# haasoscope_pro_adc_board.net
KiCad netlist of a schematic drawn in EAGLE
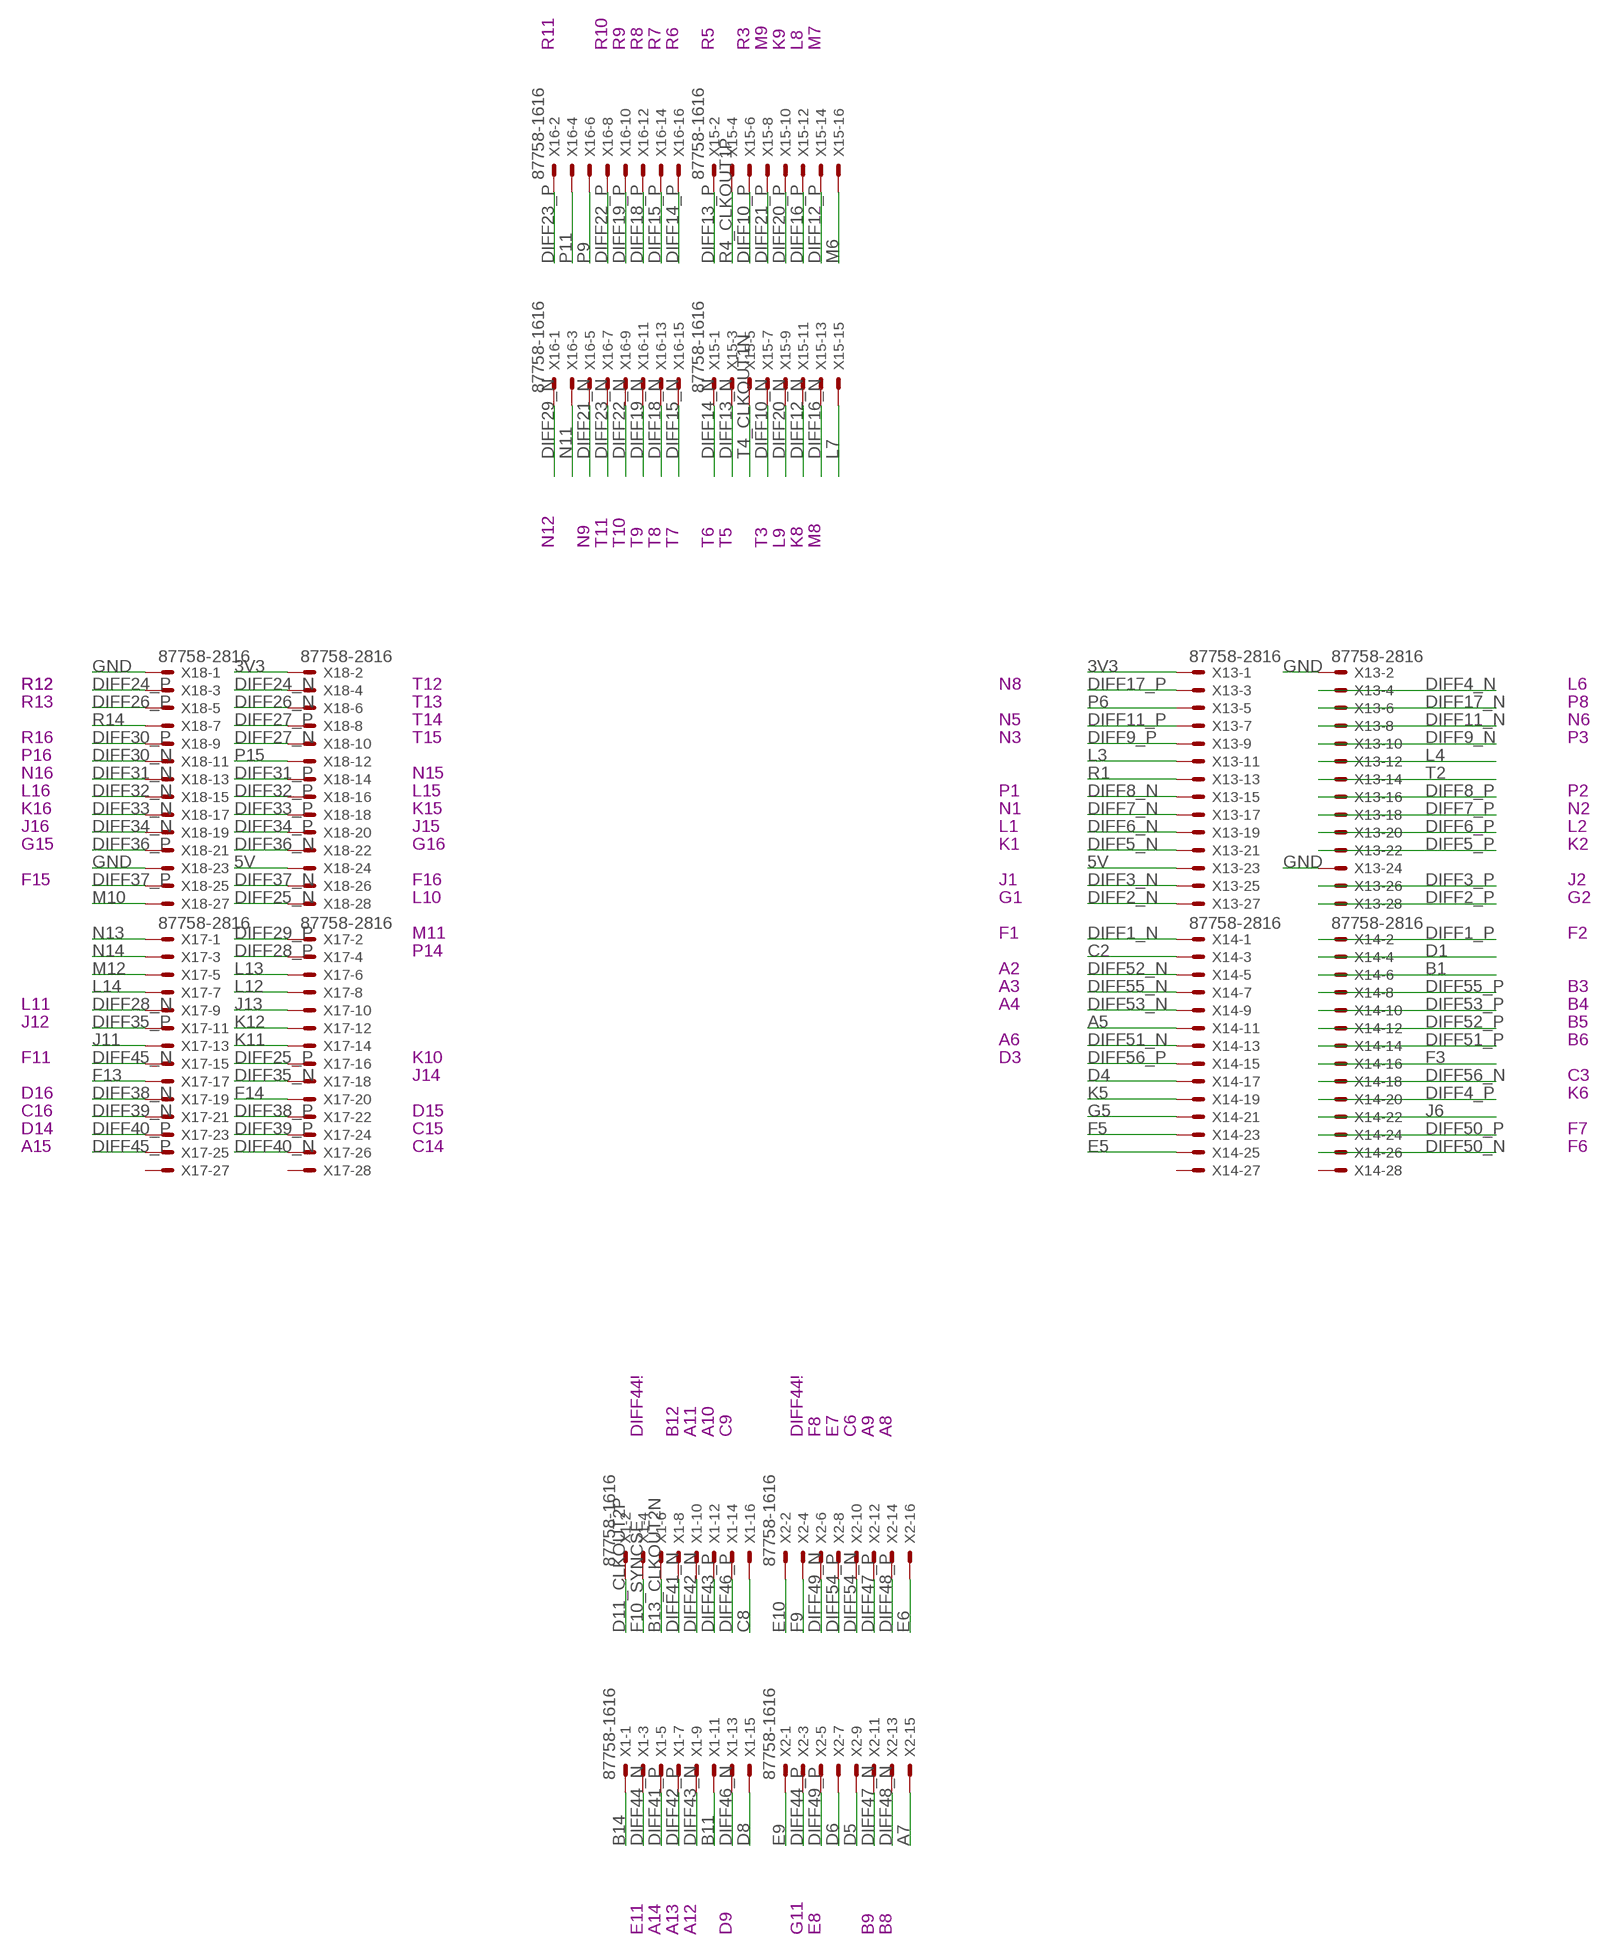
[diagram p0: schematic, sheet 1]
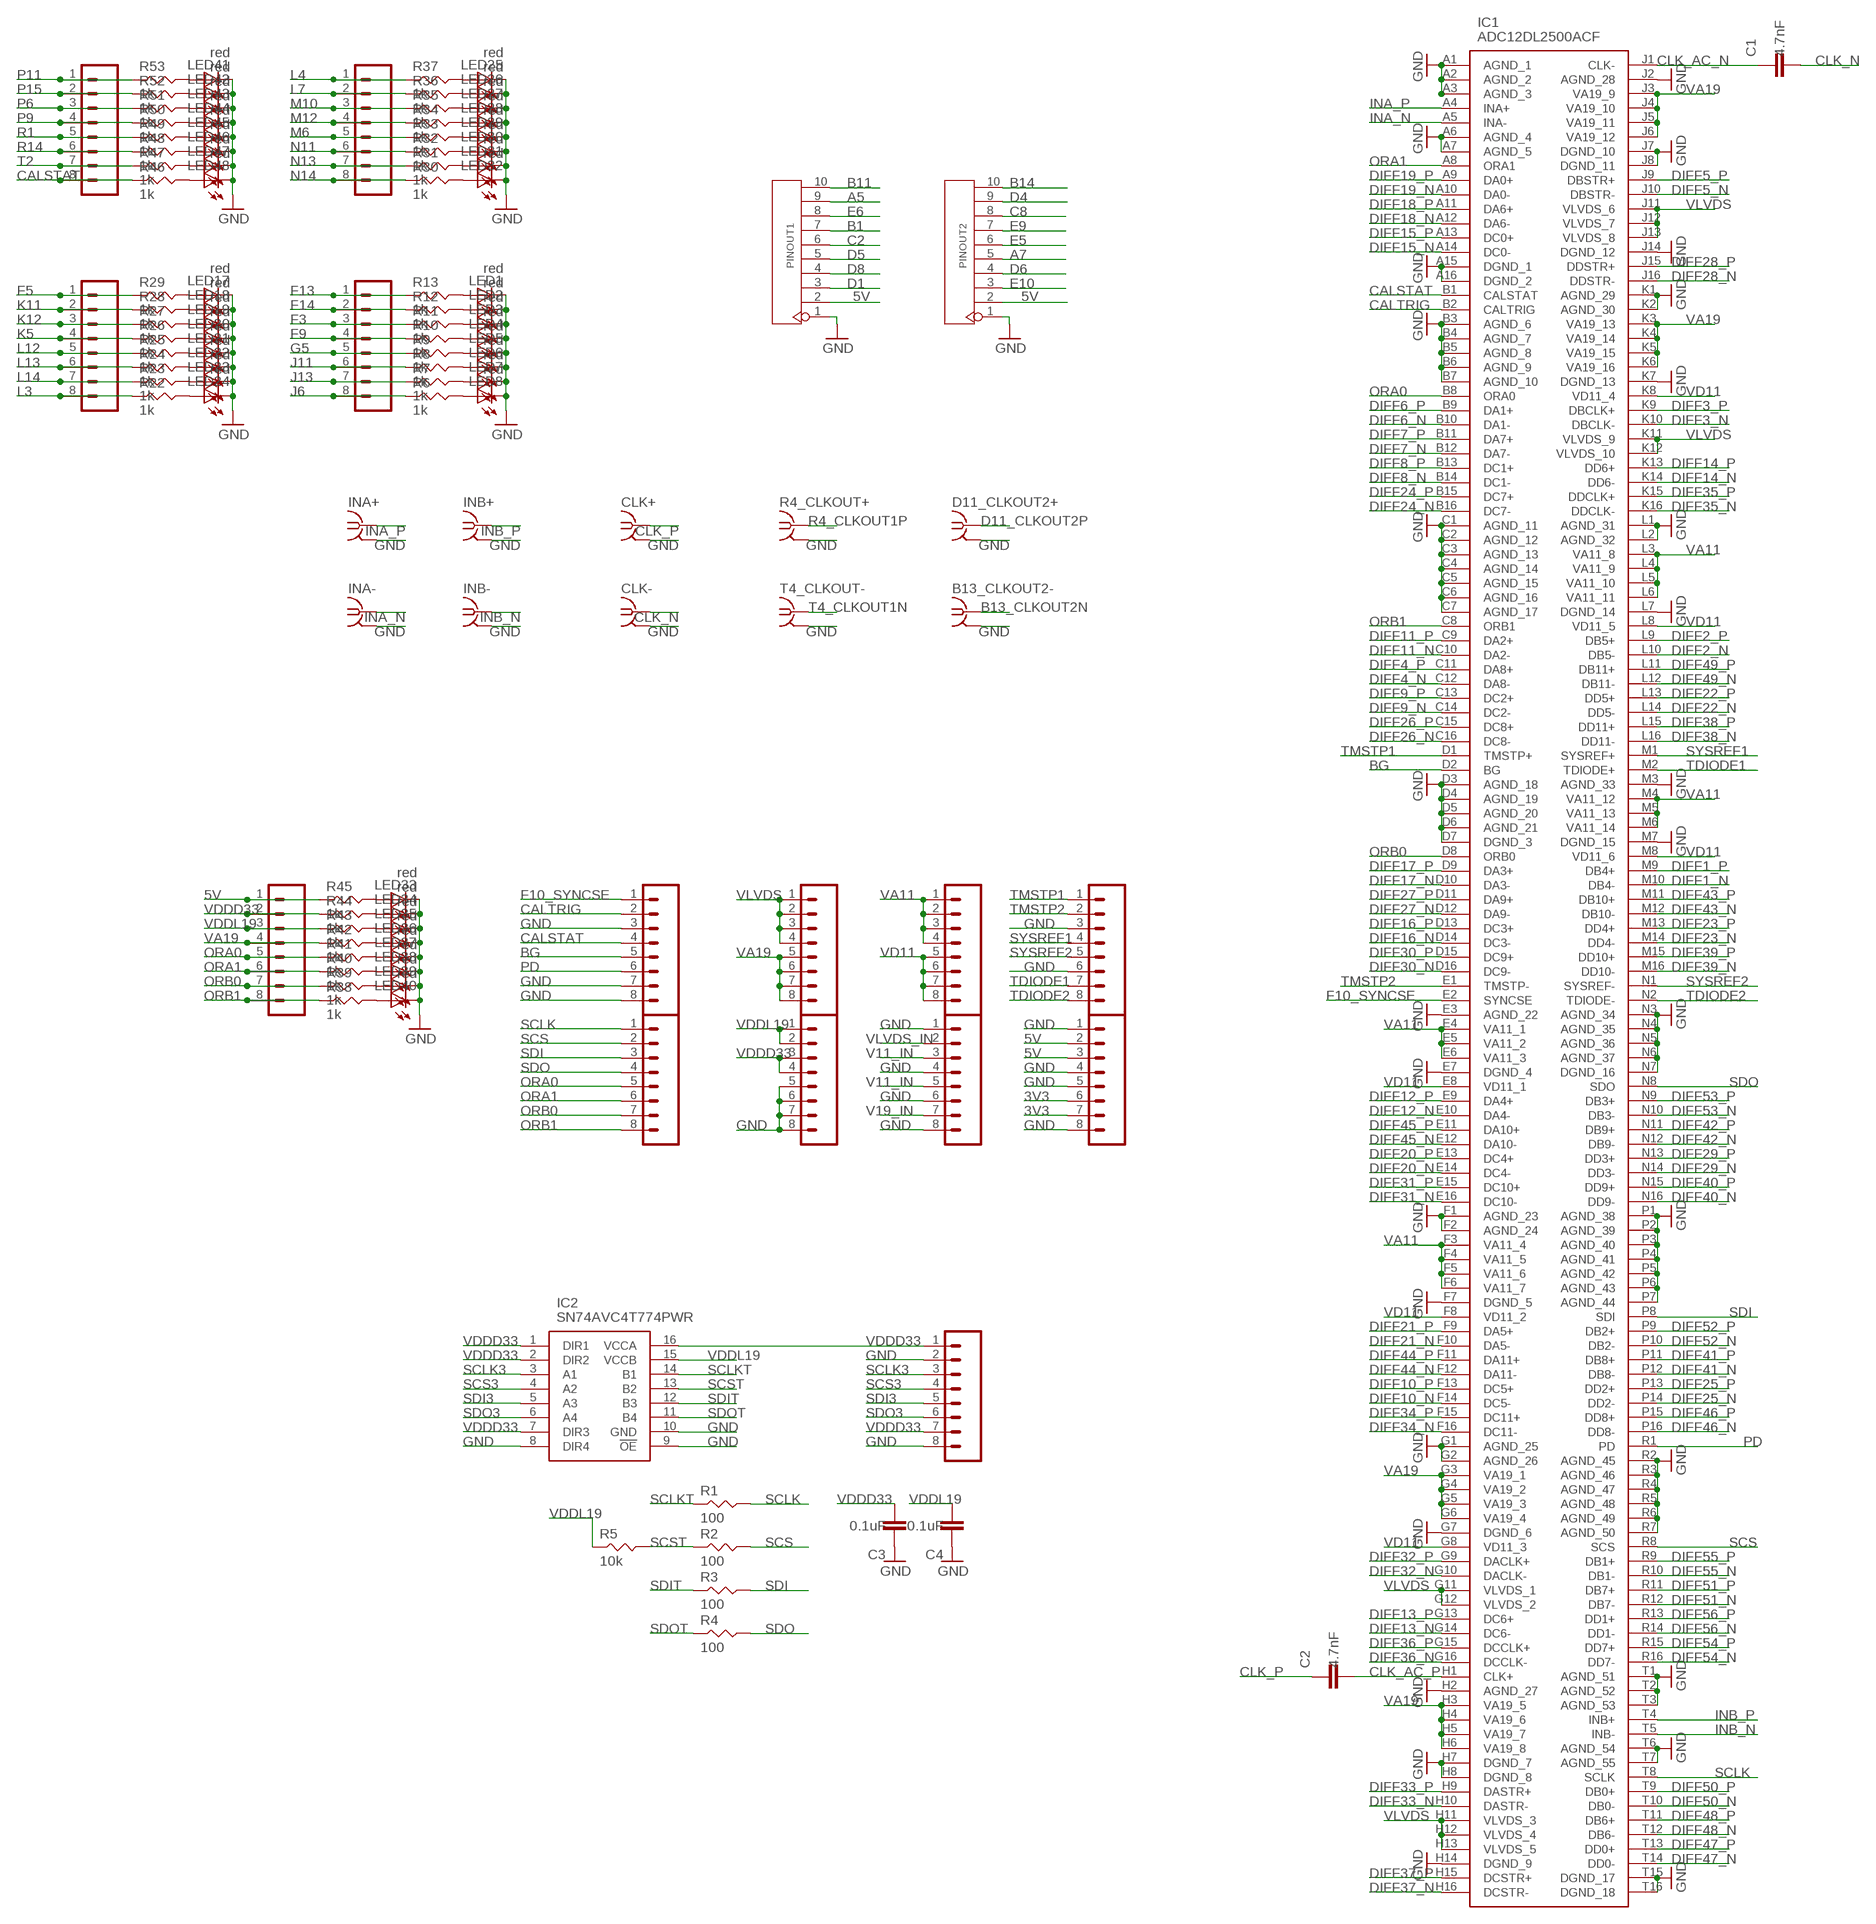
[diagram p1: schematic, sheet 2]
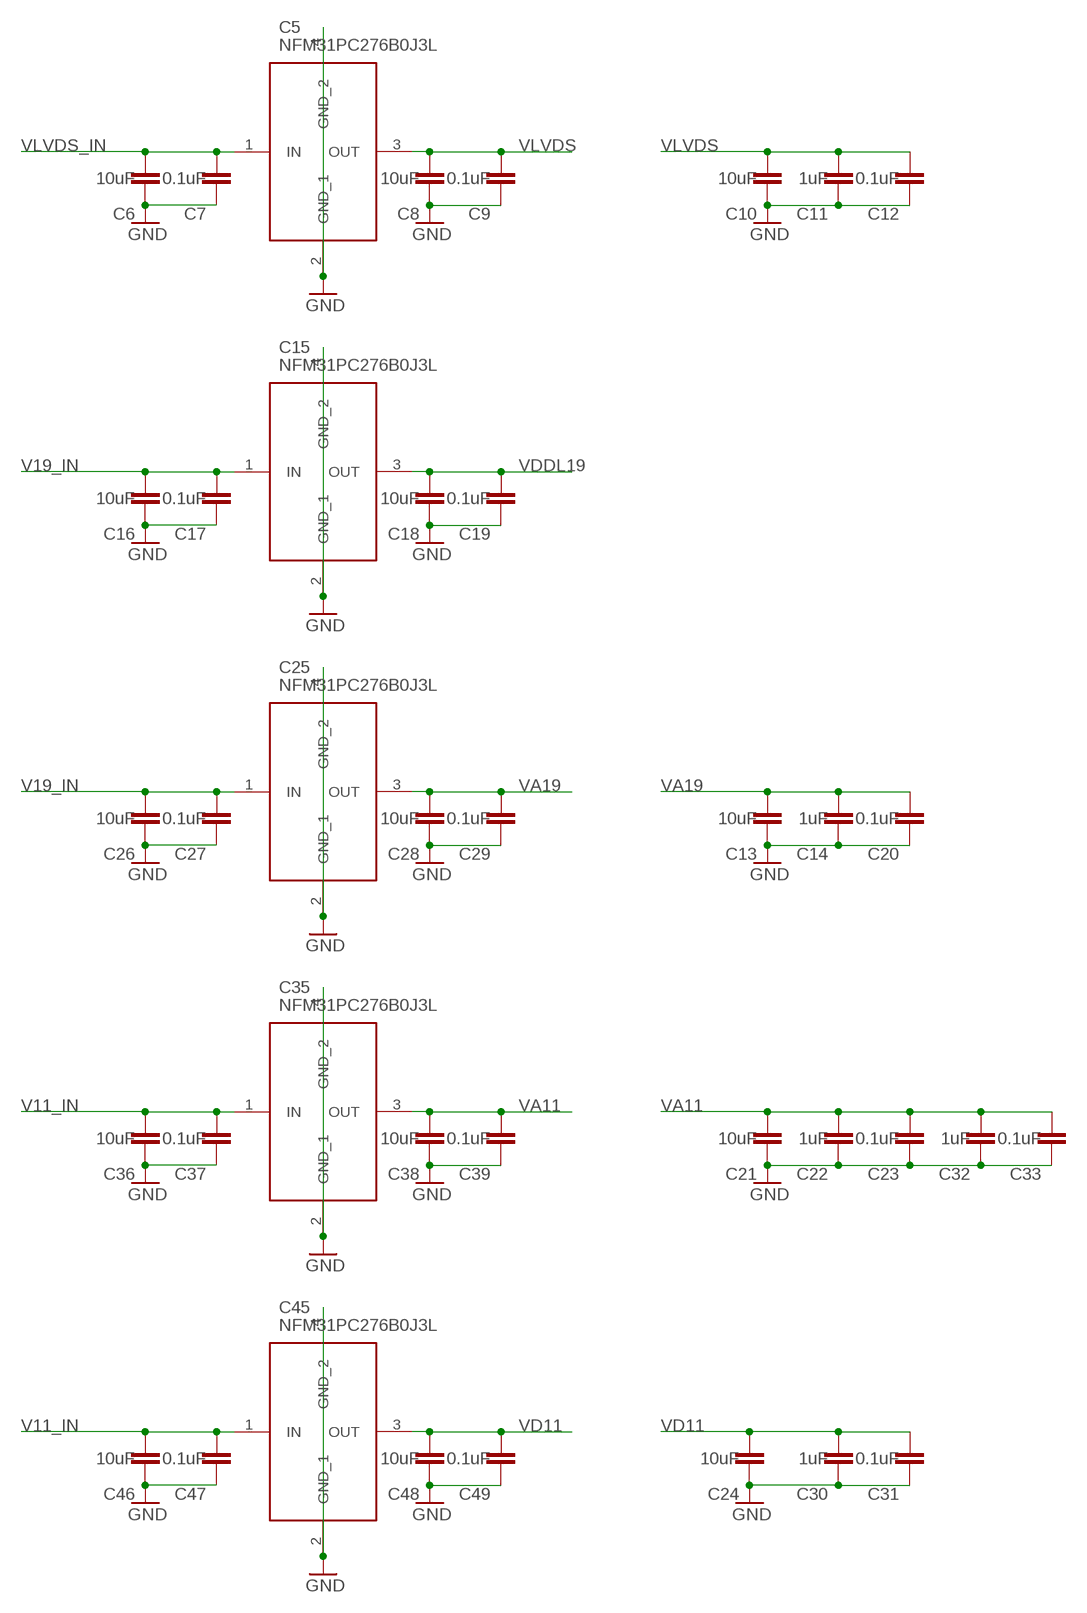
[diagram p2: schematic, sheet 3]

(export (version "E")
  (design (tool "Eeschema 10.0.6"))
  (components
    (comp (ref "X1")
      (value "87758-1616")
      (footprint "eagle-import:87758-1616")
      (fields (field (name "MF") "MOLEX"))
      (libsource (lib "eagle-import") (part "87758-1616"))
    )
    (comp (ref "X2")
      (value "87758-1616")
      (footprint "eagle-import:87758-1616")
      (fields (field (name "MF") "MOLEX"))
      (libsource (lib "eagle-import") (part "87758-1616"))
    )
    (comp (ref "X13")
      (value "87758-2816")
      (footprint "eagle-import:87758-2816")
      (fields (field (name "MF") "MOLEX"))
      (libsource (lib "eagle-import") (part "87758-2816"))
    )
    (comp (ref "X14")
      (value "87758-2816")
      (footprint "eagle-import:87758-2816")
      (fields (field (name "MF") "MOLEX"))
      (libsource (lib "eagle-import") (part "87758-2816"))
    )
    (comp (ref "X15")
      (value "87758-1616")
      (footprint "eagle-import:87758-1616")
      (fields (field (name "MF") "MOLEX"))
      (libsource (lib "eagle-import") (part "87758-1616"))
    )
    (comp (ref "X16")
      (value "87758-1616")
      (footprint "eagle-import:87758-1616")
      (fields (field (name "MF") "MOLEX"))
      (libsource (lib "eagle-import") (part "87758-1616"))
    )
    (comp (ref "X17")
      (value "87758-2816")
      (footprint "eagle-import:87758-2816")
      (fields (field (name "MF") "MOLEX"))
      (libsource (lib "eagle-import") (part "87758-2816"))
    )
    (comp (ref "X18")
      (value "87758-2816")
      (footprint "eagle-import:87758-2816")
      (fields (field (name "MF") "MOLEX"))
      (libsource (lib "eagle-import") (part "87758-2816"))
    )
    (comp (ref "B13_CLKOUT2-")
      (value "BU-SMB-V")
      (footprint "eagle-import:BU-SMB-V")
      (libsource (lib "eagle-import") (part "BU-SMB-V"))
    )
    (comp (ref "C1")
      (value "4.7nF")
      (footprint "eagle-import:RESC0402_N")
      (libsource (lib "eagle-import") (part "CAPACITOR_0402_N"))
    )
    (comp (ref "C2")
      (value "4.7nF")
      (footprint "eagle-import:RESC0402_N")
      (libsource (lib "eagle-import") (part "CAPACITOR_0402_N"))
    )
    (comp (ref "C3")
      (value "0.1uF")
      (footprint "eagle-import:RESC0402_N")
      (libsource (lib "eagle-import") (part "CAPACITOR_0402_N"))
    )
    (comp (ref "C4")
      (value "0.1uF")
      (footprint "eagle-import:RESC0402_N")
      (libsource (lib "eagle-import") (part "CAPACITOR_0402_N"))
    )
    (comp (ref "CLK+")
      (value "BU-SMB-V")
      (footprint "eagle-import:BU-SMB-V")
      (libsource (lib "eagle-import") (part "BU-SMB-V"))
    )
    (comp (ref "CLK-")
      (value "BU-SMB-V")
      (footprint "eagle-import:BU-SMB-V")
      (libsource (lib "eagle-import") (part "BU-SMB-V"))
    )
    (comp (ref "D11_CLKOUT2+")
      (value "BU-SMB-V")
      (footprint "eagle-import:BU-SMB-V")
      (libsource (lib "eagle-import") (part "BU-SMB-V"))
    )
    (comp (ref "IC1")
      (value "ADC12DL2500ACF")
      (footprint "eagle-import:BGA256C100P16X16_1700X1700X331")
      (fields (field (name "MANUFACTURER_PART_NUMBER") "ADC12DL500ACF"))
      (libsource (lib "eagle-import") (part "ADC12DL2500ACF"))
    )
    (comp (ref "IC2")
      (value "SN74AVC4T774PWR")
      (footprint "eagle-import:SOP65P640X120-16N")
      (fields (field (name "MOUSER_PART_NUMBER") "595-SN74AVC4T774PWR"))
      (libsource (lib "eagle-import") (part "SN74AVC4T774PWR"))
    )
    (comp (ref "INA+")
      (value "BU-SMB-V")
      (footprint "eagle-import:BU-SMB-V")
      (libsource (lib "eagle-import") (part "BU-SMB-V"))
    )
    (comp (ref "INA-")
      (value "BU-SMB-V")
      (footprint "eagle-import:BU-SMB-V")
      (libsource (lib "eagle-import") (part "BU-SMB-V"))
    )
    (comp (ref "INB+")
      (value "BU-SMB-V")
      (footprint "eagle-import:BU-SMB-V")
      (libsource (lib "eagle-import") (part "BU-SMB-V"))
    )
    (comp (ref "INB-")
      (value "BU-SMB-V")
      (footprint "eagle-import:BU-SMB-V")
      (libsource (lib "eagle-import") (part "BU-SMB-V"))
    )
    (comp (ref "J1")
      (value "8pin")
      (footprint "eagle-import:1X08")
      (libsource (lib "eagle-import") (part "CONN_08{dblquote}"))
    )
    (comp (ref "J2")
      (value "8pin")
      (footprint "eagle-import:1X08")
      (libsource (lib "eagle-import") (part "CONN_08{dblquote}"))
    )
    (comp (ref "J3")
      (value "8pin")
      (footprint "eagle-import:1X08")
      (libsource (lib "eagle-import") (part "CONN_08{dblquote}"))
    )
    (comp (ref "J4")
      (value "8pin")
      (footprint "eagle-import:1X08")
      (libsource (lib "eagle-import") (part "CONN_08{dblquote}"))
    )
    (comp (ref "J5")
      (value "8pin")
      (footprint "eagle-import:1X08")
      (libsource (lib "eagle-import") (part "CONN_08{dblquote}"))
    )
    (comp (ref "J6")
      (value "8pin")
      (footprint "eagle-import:1X08")
      (libsource (lib "eagle-import") (part "CONN_08{dblquote}"))
    )
    (comp (ref "J7")
      (value "8pin")
      (footprint "eagle-import:1X08")
      (libsource (lib "eagle-import") (part "CONN_08{dblquote}"))
    )
    (comp (ref "J8")
      (value "8pin")
      (footprint "eagle-import:1X08")
      (libsource (lib "eagle-import") (part "CONN_08{dblquote}"))
    )
    (comp (ref "J10")
      (value "8pin")
      (footprint "eagle-import:1X08")
      (libsource (lib "eagle-import") (part "CONN_08{dblquote}"))
    )
    (comp (ref "J11")
      (value "8pin")
      (footprint "eagle-import:1X08")
      (libsource (lib "eagle-import") (part "CONN_08{dblquote}"))
    )
    (comp (ref "J12")
      (value "8pin")
      (footprint "eagle-import:1X08")
      (libsource (lib "eagle-import") (part "CONN_08{dblquote}"))
    )
    (comp (ref "J13")
      (value "8pin")
      (footprint "eagle-import:1X08")
      (libsource (lib "eagle-import") (part "CONN_08{dblquote}"))
    )
    (comp (ref "J16")
      (value "8pin")
      (footprint "eagle-import:1X08")
      (libsource (lib "eagle-import") (part "CONN_08{dblquote}"))
    )
    (comp (ref "J17")
      (value "8pin")
      (footprint "eagle-import:1X08")
      (libsource (lib "eagle-import") (part "CONN_08{dblquote}"))
    )
    (comp (ref "LED1")
      (value "red")
      (footprint "eagle-import:CHIP-LED0603")
      (libsource (lib "eagle-import") (part "LEDCHIP-LED0603"))
    )
    (comp (ref "LED2")
      (value "red")
      (footprint "eagle-import:CHIP-LED0603")
      (libsource (lib "eagle-import") (part "LEDCHIP-LED0603"))
    )
    (comp (ref "LED3")
      (value "red")
      (footprint "eagle-import:CHIP-LED0603")
      (libsource (lib "eagle-import") (part "LEDCHIP-LED0603"))
    )
    (comp (ref "LED4")
      (value "red")
      (footprint "eagle-import:CHIP-LED0603")
      (libsource (lib "eagle-import") (part "LEDCHIP-LED0603"))
    )
    (comp (ref "LED5")
      (value "red")
      (footprint "eagle-import:CHIP-LED0603")
      (libsource (lib "eagle-import") (part "LEDCHIP-LED0603"))
    )
    (comp (ref "LED6")
      (value "red")
      (footprint "eagle-import:CHIP-LED0603")
      (libsource (lib "eagle-import") (part "LEDCHIP-LED0603"))
    )
    (comp (ref "LED7")
      (value "red")
      (footprint "eagle-import:CHIP-LED0603")
      (libsource (lib "eagle-import") (part "LEDCHIP-LED0603"))
    )
    (comp (ref "LED8")
      (value "red")
      (footprint "eagle-import:CHIP-LED0603")
      (libsource (lib "eagle-import") (part "LEDCHIP-LED0603"))
    )
    (comp (ref "LED17")
      (value "red")
      (footprint "eagle-import:CHIP-LED0603")
      (libsource (lib "eagle-import") (part "LEDCHIP-LED0603"))
    )
    (comp (ref "LED18")
      (value "red")
      (footprint "eagle-import:CHIP-LED0603")
      (libsource (lib "eagle-import") (part "LEDCHIP-LED0603"))
    )
    (comp (ref "LED19")
      (value "red")
      (footprint "eagle-import:CHIP-LED0603")
      (libsource (lib "eagle-import") (part "LEDCHIP-LED0603"))
    )
    (comp (ref "LED20")
      (value "red")
      (footprint "eagle-import:CHIP-LED0603")
      (libsource (lib "eagle-import") (part "LEDCHIP-LED0603"))
    )
    (comp (ref "LED21")
      (value "red")
      (footprint "eagle-import:CHIP-LED0603")
      (libsource (lib "eagle-import") (part "LEDCHIP-LED0603"))
    )
    (comp (ref "LED22")
      (value "red")
      (footprint "eagle-import:CHIP-LED0603")
      (libsource (lib "eagle-import") (part "LEDCHIP-LED0603"))
    )
    (comp (ref "LED23")
      (value "red")
      (footprint "eagle-import:CHIP-LED0603")
      (libsource (lib "eagle-import") (part "LEDCHIP-LED0603"))
    )
    (comp (ref "LED24")
      (value "red")
      (footprint "eagle-import:CHIP-LED0603")
      (libsource (lib "eagle-import") (part "LEDCHIP-LED0603"))
    )
    (comp (ref "LED25")
      (value "red")
      (footprint "eagle-import:CHIP-LED0603")
      (libsource (lib "eagle-import") (part "LEDCHIP-LED0603"))
    )
    (comp (ref "LED26")
      (value "red")
      (footprint "eagle-import:CHIP-LED0603")
      (libsource (lib "eagle-import") (part "LEDCHIP-LED0603"))
    )
    (comp (ref "LED27")
      (value "red")
      (footprint "eagle-import:CHIP-LED0603")
      (libsource (lib "eagle-import") (part "LEDCHIP-LED0603"))
    )
    (comp (ref "LED28")
      (value "red")
      (footprint "eagle-import:CHIP-LED0603")
      (libsource (lib "eagle-import") (part "LEDCHIP-LED0603"))
    )
    (comp (ref "LED29")
      (value "red")
      (footprint "eagle-import:CHIP-LED0603")
      (libsource (lib "eagle-import") (part "LEDCHIP-LED0603"))
    )
    (comp (ref "LED30")
      (value "red")
      (footprint "eagle-import:CHIP-LED0603")
      (libsource (lib "eagle-import") (part "LEDCHIP-LED0603"))
    )
    (comp (ref "LED31")
      (value "red")
      (footprint "eagle-import:CHIP-LED0603")
      (libsource (lib "eagle-import") (part "LEDCHIP-LED0603"))
    )
    (comp (ref "LED32")
      (value "red")
      (footprint "eagle-import:CHIP-LED0603")
      (libsource (lib "eagle-import") (part "LEDCHIP-LED0603"))
    )
    (comp (ref "LED33")
      (value "red")
      (footprint "eagle-import:CHIP-LED0603")
      (libsource (lib "eagle-import") (part "LEDCHIP-LED0603"))
    )
    (comp (ref "LED34")
      (value "red")
      (footprint "eagle-import:CHIP-LED0603")
      (libsource (lib "eagle-import") (part "LEDCHIP-LED0603"))
    )
    (comp (ref "LED35")
      (value "red")
      (footprint "eagle-import:CHIP-LED0603")
      (libsource (lib "eagle-import") (part "LEDCHIP-LED0603"))
    )
    (comp (ref "LED36")
      (value "red")
      (footprint "eagle-import:CHIP-LED0603")
      (libsource (lib "eagle-import") (part "LEDCHIP-LED0603"))
    )
    (comp (ref "LED37")
      (value "red")
      (footprint "eagle-import:CHIP-LED0603")
      (libsource (lib "eagle-import") (part "LEDCHIP-LED0603"))
    )
    (comp (ref "LED38")
      (value "red")
      (footprint "eagle-import:CHIP-LED0603")
      (libsource (lib "eagle-import") (part "LEDCHIP-LED0603"))
    )
    (comp (ref "LED39")
      (value "red")
      (footprint "eagle-import:CHIP-LED0603")
      (libsource (lib "eagle-import") (part "LEDCHIP-LED0603"))
    )
    (comp (ref "LED40")
      (value "red")
      (footprint "eagle-import:CHIP-LED0603")
      (libsource (lib "eagle-import") (part "LEDCHIP-LED0603"))
    )
    (comp (ref "LED41")
      (value "red")
      (footprint "eagle-import:CHIP-LED0603")
      (libsource (lib "eagle-import") (part "LEDCHIP-LED0603"))
    )
    (comp (ref "LED42")
      (value "red")
      (footprint "eagle-import:CHIP-LED0603")
      (libsource (lib "eagle-import") (part "LEDCHIP-LED0603"))
    )
    (comp (ref "LED43")
      (value "red")
      (footprint "eagle-import:CHIP-LED0603")
      (libsource (lib "eagle-import") (part "LEDCHIP-LED0603"))
    )
    (comp (ref "LED44")
      (value "red")
      (footprint "eagle-import:CHIP-LED0603")
      (libsource (lib "eagle-import") (part "LEDCHIP-LED0603"))
    )
    (comp (ref "LED45")
      (value "red")
      (footprint "eagle-import:CHIP-LED0603")
      (libsource (lib "eagle-import") (part "LEDCHIP-LED0603"))
    )
    (comp (ref "LED46")
      (value "red")
      (footprint "eagle-import:CHIP-LED0603")
      (libsource (lib "eagle-import") (part "LEDCHIP-LED0603"))
    )
    (comp (ref "LED47")
      (value "red")
      (footprint "eagle-import:CHIP-LED0603")
      (libsource (lib "eagle-import") (part "LEDCHIP-LED0603"))
    )
    (comp (ref "LED48")
      (value "red")
      (footprint "eagle-import:CHIP-LED0603")
      (libsource (lib "eagle-import") (part "LEDCHIP-LED0603"))
    )
    (comp (ref "PINOUT1")
      (value "YELLOW-10P-2.54")
      (footprint "eagle-import:H10-2.54")
      (fields (field (name "MPN") "F185-1110A1BSYC1"))
      (libsource (lib "eagle-import") (part "DIP-YELLOW-FEMALE-HEADER-VERT(10P-2.54)"))
    )
    (comp (ref "PINOUT2")
      (value "YELLOW-10P-2.54")
      (footprint "eagle-import:H10-2.54")
      (fields (field (name "MPN") "F185-1110A1BSYC1"))
      (libsource (lib "eagle-import") (part "DIP-YELLOW-FEMALE-HEADER-VERT(10P-2.54)"))
    )
    (comp (ref "R1")
      (value "100")
      (footprint "eagle-import:RES-0402")
      (libsource (lib "eagle-import") (part "RES-0402"))
    )
    (comp (ref "R2")
      (value "100")
      (footprint "eagle-import:RES-0402")
      (libsource (lib "eagle-import") (part "RES-0402"))
    )
    (comp (ref "R3")
      (value "100")
      (footprint "eagle-import:RES-0402")
      (libsource (lib "eagle-import") (part "RES-0402"))
    )
    (comp (ref "R4")
      (value "100")
      (footprint "eagle-import:RES-0402")
      (libsource (lib "eagle-import") (part "RES-0402"))
    )
    (comp (ref "R4_CLKOUT+")
      (value "BU-SMB-V")
      (footprint "eagle-import:BU-SMB-V")
      (libsource (lib "eagle-import") (part "BU-SMB-V"))
    )
    (comp (ref "R5")
      (value "10k")
      (footprint "eagle-import:RES-0402")
      (libsource (lib "eagle-import") (part "RES-0402"))
    )
    (comp (ref "R6")
      (value "1k")
      (footprint "eagle-import:RES-0402")
      (libsource (lib "eagle-import") (part "RES-0402"))
    )
    (comp (ref "R7")
      (value "1k")
      (footprint "eagle-import:RES-0402")
      (libsource (lib "eagle-import") (part "RES-0402"))
    )
    (comp (ref "R8")
      (value "1k")
      (footprint "eagle-import:RES-0402")
      (libsource (lib "eagle-import") (part "RES-0402"))
    )
    (comp (ref "R9")
      (value "1k")
      (footprint "eagle-import:RES-0402")
      (libsource (lib "eagle-import") (part "RES-0402"))
    )
    (comp (ref "R10")
      (value "1k")
      (footprint "eagle-import:RES-0402")
      (libsource (lib "eagle-import") (part "RES-0402"))
    )
    (comp (ref "R11")
      (value "1k")
      (footprint "eagle-import:RES-0402")
      (libsource (lib "eagle-import") (part "RES-0402"))
    )
    (comp (ref "R12")
      (value "1k")
      (footprint "eagle-import:RES-0402")
      (libsource (lib "eagle-import") (part "RES-0402"))
    )
    (comp (ref "R13")
      (value "1k")
      (footprint "eagle-import:RES-0402")
      (libsource (lib "eagle-import") (part "RES-0402"))
    )
    (comp (ref "R22")
      (value "1k")
      (footprint "eagle-import:RES-0402")
      (libsource (lib "eagle-import") (part "RES-0402"))
    )
    (comp (ref "R23")
      (value "1k")
      (footprint "eagle-import:RES-0402")
      (libsource (lib "eagle-import") (part "RES-0402"))
    )
    (comp (ref "R24")
      (value "1k")
      (footprint "eagle-import:RES-0402")
      (libsource (lib "eagle-import") (part "RES-0402"))
    )
    (comp (ref "R25")
      (value "1k")
      (footprint "eagle-import:RES-0402")
      (libsource (lib "eagle-import") (part "RES-0402"))
    )
    (comp (ref "R26")
      (value "1k")
      (footprint "eagle-import:RES-0402")
      (libsource (lib "eagle-import") (part "RES-0402"))
    )
    (comp (ref "R27")
      (value "1k")
      (footprint "eagle-import:RES-0402")
      (libsource (lib "eagle-import") (part "RES-0402"))
    )
    (comp (ref "R28")
      (value "1k")
      (footprint "eagle-import:RES-0402")
      (libsource (lib "eagle-import") (part "RES-0402"))
    )
    (comp (ref "R29")
      (value "1k")
      (footprint "eagle-import:RES-0402")
      (libsource (lib "eagle-import") (part "RES-0402"))
    )
    (comp (ref "R30")
      (value "1k")
      (footprint "eagle-import:RES-0402")
      (libsource (lib "eagle-import") (part "RES-0402"))
    )
    (comp (ref "R31")
      (value "1k")
      (footprint "eagle-import:RES-0402")
      (libsource (lib "eagle-import") (part "RES-0402"))
    )
    (comp (ref "R32")
      (value "1k")
      (footprint "eagle-import:RES-0402")
      (libsource (lib "eagle-import") (part "RES-0402"))
    )
    (comp (ref "R33")
      (value "1k")
      (footprint "eagle-import:RES-0402")
      (libsource (lib "eagle-import") (part "RES-0402"))
    )
    (comp (ref "R34")
      (value "1k")
      (footprint "eagle-import:RES-0402")
      (libsource (lib "eagle-import") (part "RES-0402"))
    )
    (comp (ref "R35")
      (value "1k")
      (footprint "eagle-import:RES-0402")
      (libsource (lib "eagle-import") (part "RES-0402"))
    )
    (comp (ref "R36")
      (value "1k")
      (footprint "eagle-import:RES-0402")
      (libsource (lib "eagle-import") (part "RES-0402"))
    )
    (comp (ref "R37")
      (value "1k")
      (footprint "eagle-import:RES-0402")
      (libsource (lib "eagle-import") (part "RES-0402"))
    )
    (comp (ref "R38")
      (value "1k")
      (footprint "eagle-import:RES-0402")
      (libsource (lib "eagle-import") (part "RES-0402"))
    )
    (comp (ref "R39")
      (value "1k")
      (footprint "eagle-import:RES-0402")
      (libsource (lib "eagle-import") (part "RES-0402"))
    )
    (comp (ref "R40")
      (value "1k")
      (footprint "eagle-import:RES-0402")
      (libsource (lib "eagle-import") (part "RES-0402"))
    )
    (comp (ref "R41")
      (value "1k")
      (footprint "eagle-import:RES-0402")
      (libsource (lib "eagle-import") (part "RES-0402"))
    )
    (comp (ref "R42")
      (value "1k")
      (footprint "eagle-import:RES-0402")
      (libsource (lib "eagle-import") (part "RES-0402"))
    )
    (comp (ref "R43")
      (value "1k")
      (footprint "eagle-import:RES-0402")
      (libsource (lib "eagle-import") (part "RES-0402"))
    )
    (comp (ref "R44")
      (value "1k")
      (footprint "eagle-import:RES-0402")
      (libsource (lib "eagle-import") (part "RES-0402"))
    )
    (comp (ref "R45")
      (value "1k")
      (footprint "eagle-import:RES-0402")
      (libsource (lib "eagle-import") (part "RES-0402"))
    )
    (comp (ref "R46")
      (value "1k")
      (footprint "eagle-import:RES-0402")
      (libsource (lib "eagle-import") (part "RES-0402"))
    )
    (comp (ref "R47")
      (value "1k")
      (footprint "eagle-import:RES-0402")
      (libsource (lib "eagle-import") (part "RES-0402"))
    )
    (comp (ref "R48")
      (value "1k")
      (footprint "eagle-import:RES-0402")
      (libsource (lib "eagle-import") (part "RES-0402"))
    )
    (comp (ref "R49")
      (value "1k")
      (footprint "eagle-import:RES-0402")
      (libsource (lib "eagle-import") (part "RES-0402"))
    )
    (comp (ref "R50")
      (value "1k")
      (footprint "eagle-import:RES-0402")
      (libsource (lib "eagle-import") (part "RES-0402"))
    )
    (comp (ref "R51")
      (value "1k")
      (footprint "eagle-import:RES-0402")
      (libsource (lib "eagle-import") (part "RES-0402"))
    )
    (comp (ref "R52")
      (value "1k")
      (footprint "eagle-import:RES-0402")
      (libsource (lib "eagle-import") (part "RES-0402"))
    )
    (comp (ref "R53")
      (value "1k")
      (footprint "eagle-import:RES-0402")
      (libsource (lib "eagle-import") (part "RES-0402"))
    )
    (comp (ref "T4_CLKOUT-")
      (value "BU-SMB-V")
      (footprint "eagle-import:BU-SMB-V")
      (libsource (lib "eagle-import") (part "BU-SMB-V"))
    )
    (comp (ref "C5")
      (value "NFM31PC276B0J3L")
      (footprint "eagle-import:NFM31HK103R1H3L")
      (fields (field (name "MOUSER_PART_NUMBER") "81-NFM31PC276B0J3L"))
      (libsource (lib "eagle-import") (part "NFM31PC276B0J3L"))
    )
    (comp (ref "C6")
      (value "10uF")
      (footprint "eagle-import:RESC0805_N")
      (libsource (lib "eagle-import") (part "CAPACITOR_0805_N"))
    )
    (comp (ref "C7")
      (value "0.1uF")
      (footprint "eagle-import:RESC0402_N")
      (libsource (lib "eagle-import") (part "CAPACITOR_0402_N"))
    )
    (comp (ref "C8")
      (value "10uF")
      (footprint "eagle-import:RESC0805_N")
      (libsource (lib "eagle-import") (part "CAPACITOR_0805_N"))
    )
    (comp (ref "C9")
      (value "0.1uF")
      (footprint "eagle-import:RESC0402_N")
      (libsource (lib "eagle-import") (part "CAPACITOR_0402_N"))
    )
    (comp (ref "C10")
      (value "10uF")
      (footprint "eagle-import:RESC0805_N")
      (libsource (lib "eagle-import") (part "CAPACITOR_0805_N"))
    )
    (comp (ref "C11")
      (value "1uF")
      (footprint "eagle-import:RESC0402_N")
      (libsource (lib "eagle-import") (part "CAPACITOR_0402_N"))
    )
    (comp (ref "C12")
      (value "0.1uF")
      (footprint "eagle-import:RESC0402_N")
      (libsource (lib "eagle-import") (part "CAPACITOR_0402_N"))
    )
    (comp (ref "C13")
      (value "10uF")
      (footprint "eagle-import:RESC0805_N")
      (libsource (lib "eagle-import") (part "CAPACITOR_0805_N"))
    )
    (comp (ref "C14")
      (value "1uF")
      (footprint "eagle-import:RESC0402_N")
      (libsource (lib "eagle-import") (part "CAPACITOR_0402_N"))
    )
    (comp (ref "C15")
      (value "NFM31PC276B0J3L")
      (footprint "eagle-import:NFM31HK103R1H3L")
      (fields (field (name "MOUSER_PART_NUMBER") "81-NFM31PC276B0J3L"))
      (libsource (lib "eagle-import") (part "NFM31PC276B0J3L"))
    )
    (comp (ref "C16")
      (value "10uF")
      (footprint "eagle-import:RESC0805_N")
      (libsource (lib "eagle-import") (part "CAPACITOR_0805_N"))
    )
    (comp (ref "C17")
      (value "0.1uF")
      (footprint "eagle-import:RESC0402_N")
      (libsource (lib "eagle-import") (part "CAPACITOR_0402_N"))
    )
    (comp (ref "C18")
      (value "10uF")
      (footprint "eagle-import:RESC0805_N")
      (libsource (lib "eagle-import") (part "CAPACITOR_0805_N"))
    )
    (comp (ref "C19")
      (value "0.1uF")
      (footprint "eagle-import:RESC0402_N")
      (libsource (lib "eagle-import") (part "CAPACITOR_0402_N"))
    )
    (comp (ref "C20")
      (value "0.1uF")
      (footprint "eagle-import:RESC0402_N")
      (libsource (lib "eagle-import") (part "CAPACITOR_0402_N"))
    )
    (comp (ref "C21")
      (value "10uF")
      (footprint "eagle-import:RESC0805_N")
      (libsource (lib "eagle-import") (part "CAPACITOR_0805_N"))
    )
    (comp (ref "C22")
      (value "1uF")
      (footprint "eagle-import:RESC0402_N")
      (libsource (lib "eagle-import") (part "CAPACITOR_0402_N"))
    )
    (comp (ref "C23")
      (value "0.1uF")
      (footprint "eagle-import:RESC0402_N")
      (libsource (lib "eagle-import") (part "CAPACITOR_0402_N"))
    )
    (comp (ref "C24")
      (value "10uF")
      (footprint "eagle-import:RESC0805_N")
      (libsource (lib "eagle-import") (part "CAPACITOR_0805_N"))
    )
    (comp (ref "C25")
      (value "NFM31PC276B0J3L")
      (footprint "eagle-import:NFM31HK103R1H3L")
      (fields (field (name "MOUSER_PART_NUMBER") "81-NFM31PC276B0J3L"))
      (libsource (lib "eagle-import") (part "NFM31PC276B0J3L"))
    )
    (comp (ref "C26")
      (value "10uF")
      (footprint "eagle-import:RESC0805_N")
      (libsource (lib "eagle-import") (part "CAPACITOR_0805_N"))
    )
    (comp (ref "C27")
      (value "0.1uF")
      (footprint "eagle-import:RESC0402_N")
      (libsource (lib "eagle-import") (part "CAPACITOR_0402_N"))
    )
    (comp (ref "C28")
      (value "10uF")
      (footprint "eagle-import:RESC0805_N")
      (libsource (lib "eagle-import") (part "CAPACITOR_0805_N"))
    )
    (comp (ref "C29")
      (value "0.1uF")
      (footprint "eagle-import:RESC0402_N")
      (libsource (lib "eagle-import") (part "CAPACITOR_0402_N"))
    )
    (comp (ref "C30")
      (value "1uF")
      (footprint "eagle-import:RESC0402_N")
      (libsource (lib "eagle-import") (part "CAPACITOR_0402_N"))
    )
    (comp (ref "C31")
      (value "0.1uF")
      (footprint "eagle-import:RESC0402_N")
      (libsource (lib "eagle-import") (part "CAPACITOR_0402_N"))
    )
    (comp (ref "C32")
      (value "1uF")
      (footprint "eagle-import:RESC0402_N")
      (libsource (lib "eagle-import") (part "CAPACITOR_0402_N"))
    )
    (comp (ref "C33")
      (value "0.1uF")
      (footprint "eagle-import:RESC0402_N")
      (libsource (lib "eagle-import") (part "CAPACITOR_0402_N"))
    )
    (comp (ref "C35")
      (value "NFM31PC276B0J3L")
      (footprint "eagle-import:NFM31HK103R1H3L")
      (fields (field (name "MOUSER_PART_NUMBER") "81-NFM31PC276B0J3L"))
      (libsource (lib "eagle-import") (part "NFM31PC276B0J3L"))
    )
    (comp (ref "C36")
      (value "10uF")
      (footprint "eagle-import:RESC0805_N")
      (libsource (lib "eagle-import") (part "CAPACITOR_0805_N"))
    )
    (comp (ref "C37")
      (value "0.1uF")
      (footprint "eagle-import:RESC0402_N")
      (libsource (lib "eagle-import") (part "CAPACITOR_0402_N"))
    )
    (comp (ref "C38")
      (value "10uF")
      (footprint "eagle-import:RESC0805_N")
      (libsource (lib "eagle-import") (part "CAPACITOR_0805_N"))
    )
    (comp (ref "C39")
      (value "0.1uF")
      (footprint "eagle-import:RESC0402_N")
      (libsource (lib "eagle-import") (part "CAPACITOR_0402_N"))
    )
    (comp (ref "C45")
      (value "NFM31PC276B0J3L")
      (footprint "eagle-import:NFM31HK103R1H3L")
      (fields (field (name "MOUSER_PART_NUMBER") "81-NFM31PC276B0J3L"))
      (libsource (lib "eagle-import") (part "NFM31PC276B0J3L"))
    )
    (comp (ref "C46")
      (value "10uF")
      (footprint "eagle-import:RESC0805_N")
      (libsource (lib "eagle-import") (part "CAPACITOR_0805_N"))
    )
    (comp (ref "C47")
      (value "0.1uF")
      (footprint "eagle-import:RESC0402_N")
      (libsource (lib "eagle-import") (part "CAPACITOR_0402_N"))
    )
    (comp (ref "C48")
      (value "10uF")
      (footprint "eagle-import:RESC0805_N")
      (libsource (lib "eagle-import") (part "CAPACITOR_0805_N"))
    )
    (comp (ref "C49")
      (value "0.1uF")
      (footprint "eagle-import:RESC0402_N")
      (libsource (lib "eagle-import") (part "CAPACITOR_0402_N"))
    )
  )
  (nets
    (net (code "1") (name "3V3") (class "Default")
      (node (ref "J6") (pin "6") (pinfunction "6_6") (pintype "passive"))
      (node (ref "J6") (pin "7") (pinfunction "7_7") (pintype "passive"))
      (node (ref "X13") (pin "1") (pinfunction "S_1") (pintype "passive"))
      (node (ref "X18") (pin "2") (pinfunction "S_2") (pintype "passive"))
    )
    (net (code "2") (name "5V") (class "Default")
      (node (ref "J12") (pin "1") (pinfunction "1_1") (pintype "passive"))
      (node (ref "J6") (pin "2") (pinfunction "2_2") (pintype "passive"))
      (node (ref "J6") (pin "3") (pinfunction "3_3") (pintype "passive"))
      (node (ref "PINOUT1") (pin "2") (pinfunction "2_2") (pintype "bidirectional"))
      (node (ref "PINOUT2") (pin "2") (pinfunction "2_2") (pintype "bidirectional"))
      (node (ref "R45") (pin "P$1") (pinfunction "P$1_P$1") (pintype "bidirectional"))
      (node (ref "X13") (pin "23") (pinfunction "S_23") (pintype "passive"))
      (node (ref "X18") (pin "24") (pinfunction "S_24") (pintype "passive"))
    )
    (net (code "3") (name "A5") (class "Default")
      (node (ref "PINOUT1") (pin "9") (pinfunction "9_9") (pintype "bidirectional"))
      (node (ref "X14") (pin "11") (pinfunction "S_11") (pintype "passive"))
    )
    (net (code "4") (name "A7") (class "Default")
      (node (ref "PINOUT2") (pin "5") (pinfunction "5_5") (pintype "bidirectional"))
      (node (ref "X2") (pin "15") (pinfunction "S_15") (pintype "passive"))
    )
    (net (code "5") (name "B1") (class "Default")
      (node (ref "PINOUT1") (pin "7") (pinfunction "7_7") (pintype "bidirectional"))
      (node (ref "X14") (pin "6") (pinfunction "S_6") (pintype "passive"))
    )
    (net (code "6") (name "B11") (class "Default")
      (node (ref "PINOUT1") (pin "10") (pinfunction "10_10") (pintype "bidirectional"))
      (node (ref "X1") (pin "11") (pinfunction "S_11") (pintype "passive"))
    )
    (net (code "7") (name "B13_CLKOUT2N") (class "Default")
      (node (ref "B13_CLKOUT2-") (pin "1") (pinfunction "1_1") (pintype "passive"))
      (node (ref "X1") (pin "6") (pinfunction "S_6") (pintype "passive"))
    )
    (net (code "8") (name "B14") (class "Default")
      (node (ref "PINOUT2") (pin "10") (pinfunction "10_10") (pintype "bidirectional"))
      (node (ref "X1") (pin "1") (pinfunction "S_1") (pintype "passive"))
    )
    (net (code "9") (name "BG") (class "Default")
      (node (ref "IC1") (pin "D2") (pinfunction "BG_D2") (pintype "bidirectional"))
      (node (ref "J17") (pin "5") (pinfunction "5_5") (pintype "passive"))
    )
    (net (code "10") (name "C2") (class "Default")
      (node (ref "PINOUT1") (pin "6") (pinfunction "6_6") (pintype "bidirectional"))
      (node (ref "X14") (pin "3") (pinfunction "S_3") (pintype "passive"))
    )
    (net (code "11") (name "C8") (class "Default")
      (node (ref "PINOUT2") (pin "8") (pinfunction "8_8") (pintype "bidirectional"))
      (node (ref "X1") (pin "16") (pinfunction "S_16") (pintype "passive"))
    )
    (net (code "12") (name "CALSTAT") (class "Default")
      (node (ref "IC1") (pin "B1") (pinfunction "CALSTAT_B1") (pintype "bidirectional"))
      (node (ref "J13") (pin "8") (pinfunction "8_8") (pintype "passive"))
      (node (ref "J17") (pin "4") (pinfunction "4_4") (pintype "passive"))
      (node (ref "R46") (pin "P$1") (pinfunction "P$1_P$1") (pintype "bidirectional"))
    )
    (net (code "13") (name "CALTRIG") (class "Default")
      (node (ref "IC1") (pin "B2") (pinfunction "CALTRIG_B2") (pintype "bidirectional"))
      (node (ref "J17") (pin "2") (pinfunction "2_2") (pintype "passive"))
    )
    (net (code "14") (name "CLK_AC_N") (class "Default")
      (node (ref "C1") (pin "1") (pinfunction "1_1") (pintype "passive"))
      (node (ref "IC1") (pin "J1") (pinfunction "CLK-_J1") (pintype "bidirectional"))
    )
    (net (code "15") (name "CLK_AC_P") (class "Default")
      (node (ref "C2") (pin "2") (pinfunction "2_2") (pintype "passive"))
      (node (ref "IC1") (pin "H1") (pinfunction "CLK+_H1") (pintype "bidirectional"))
    )
    (net (code "16") (name "CLK_N") (class "Default")
      (node (ref "C1") (pin "2") (pinfunction "2_2") (pintype "passive"))
      (node (ref "CLK-") (pin "1") (pinfunction "1_1") (pintype "passive"))
    )
    (net (code "17") (name "CLK_P") (class "Default")
      (node (ref "C2") (pin "1") (pinfunction "1_1") (pintype "passive"))
      (node (ref "CLK+") (pin "1") (pinfunction "1_1") (pintype "passive"))
    )
    (net (code "18") (name "D1") (class "Default")
      (node (ref "PINOUT1") (pin "3") (pinfunction "3_3") (pintype "bidirectional"))
      (node (ref "X14") (pin "4") (pinfunction "S_4") (pintype "passive"))
    )
    (net (code "19") (name "D4") (class "Default")
      (node (ref "PINOUT2") (pin "9") (pinfunction "9_9") (pintype "bidirectional"))
      (node (ref "X14") (pin "17") (pinfunction "S_17") (pintype "passive"))
    )
    (net (code "20") (name "D5") (class "Default")
      (node (ref "PINOUT1") (pin "5") (pinfunction "5_5") (pintype "bidirectional"))
      (node (ref "X2") (pin "9") (pinfunction "S_9") (pintype "passive"))
    )
    (net (code "21") (name "D6") (class "Default")
      (node (ref "PINOUT2") (pin "4") (pinfunction "4_4") (pintype "bidirectional"))
      (node (ref "X2") (pin "7") (pinfunction "S_7") (pintype "passive"))
    )
    (net (code "22") (name "D8") (class "Default")
      (node (ref "PINOUT1") (pin "4") (pinfunction "4_4") (pintype "bidirectional"))
      (node (ref "X1") (pin "15") (pinfunction "S_15") (pintype "passive"))
    )
    (net (code "23") (name "D11_CLKOUT2P") (class "Default")
      (node (ref "D11_CLKOUT2+") (pin "1") (pinfunction "1_1") (pintype "passive"))
      (node (ref "X1") (pin "2") (pinfunction "S_2") (pintype "passive"))
    )
    (net (code "24") (name "DIFF1_N") (class "Default")
      (node (ref "IC1") (pin "M10") (pinfunction "DB4-_M10") (pintype "bidirectional"))
      (node (ref "X14") (pin "1") (pinfunction "S_1") (pintype "passive"))
    )
    (net (code "25") (name "DIFF1_P") (class "Default")
      (node (ref "IC1") (pin "M9") (pinfunction "DB4+_M9") (pintype "bidirectional"))
      (node (ref "X14") (pin "2") (pinfunction "S_2") (pintype "passive"))
    )
    (net (code "26") (name "DIFF2_N") (class "Default")
      (node (ref "IC1") (pin "L10") (pinfunction "DB5-_L10") (pintype "bidirectional"))
      (node (ref "X13") (pin "27") (pinfunction "S_27") (pintype "passive"))
    )
    (net (code "27") (name "DIFF2_P") (class "Default")
      (node (ref "IC1") (pin "L9") (pinfunction "DB5+_L9") (pintype "bidirectional"))
      (node (ref "X13") (pin "28") (pinfunction "S_28") (pintype "passive"))
    )
    (net (code "28") (name "DIFF3_N") (class "Default")
      (node (ref "IC1") (pin "K10") (pinfunction "DBCLK-_K10") (pintype "bidirectional"))
      (node (ref "X13") (pin "25") (pinfunction "S_25") (pintype "passive"))
    )
    (net (code "29") (name "DIFF3_P") (class "Default")
      (node (ref "IC1") (pin "K9") (pinfunction "DBCLK+_K9") (pintype "bidirectional"))
      (node (ref "X13") (pin "26") (pinfunction "S_26") (pintype "passive"))
    )
    (net (code "30") (name "DIFF4_N") (class "Default")
      (node (ref "IC1") (pin "C12") (pinfunction "DA8-_C12") (pintype "bidirectional"))
      (node (ref "X13") (pin "4") (pinfunction "S_4") (pintype "passive"))
    )
    (net (code "31") (name "DIFF4_P") (class "Default")
      (node (ref "IC1") (pin "C11") (pinfunction "DA8+_C11") (pintype "bidirectional"))
      (node (ref "X14") (pin "20") (pinfunction "S_20") (pintype "passive"))
    )
    (net (code "32") (name "DIFF5_N") (class "Default")
      (node (ref "IC1") (pin "J10") (pinfunction "DBSTR-_J10") (pintype "bidirectional"))
      (node (ref "X13") (pin "21") (pinfunction "S_21") (pintype "passive"))
    )
    (net (code "33") (name "DIFF5_P") (class "Default")
      (node (ref "IC1") (pin "J9") (pinfunction "DBSTR+_J9") (pintype "bidirectional"))
      (node (ref "X13") (pin "22") (pinfunction "S_22") (pintype "passive"))
    )
    (net (code "34") (name "DIFF6_N") (class "Default")
      (node (ref "IC1") (pin "B10") (pinfunction "DA1-_B10") (pintype "bidirectional"))
      (node (ref "X13") (pin "19") (pinfunction "S_19") (pintype "passive"))
    )
    (net (code "35") (name "DIFF6_P") (class "Default")
      (node (ref "IC1") (pin "B9") (pinfunction "DA1+_B9") (pintype "bidirectional"))
      (node (ref "X13") (pin "20") (pinfunction "S_20") (pintype "passive"))
    )
    (net (code "36") (name "DIFF7_N") (class "Default")
      (node (ref "IC1") (pin "B12") (pinfunction "DA7-_B12") (pintype "bidirectional"))
      (node (ref "X13") (pin "17") (pinfunction "S_17") (pintype "passive"))
    )
    (net (code "37") (name "DIFF7_P") (class "Default")
      (node (ref "IC1") (pin "B11") (pinfunction "DA7+_B11") (pintype "bidirectional"))
      (node (ref "X13") (pin "18") (pinfunction "S_18") (pintype "passive"))
    )
    (net (code "38") (name "DIFF8_N") (class "Default")
      (node (ref "IC1") (pin "B14") (pinfunction "DC1-_B14") (pintype "bidirectional"))
      (node (ref "X13") (pin "15") (pinfunction "S_15") (pintype "passive"))
    )
    (net (code "39") (name "DIFF8_P") (class "Default")
      (node (ref "IC1") (pin "B13") (pinfunction "DC1+_B13") (pintype "bidirectional"))
      (node (ref "X13") (pin "16") (pinfunction "S_16") (pintype "passive"))
    )
    (net (code "40") (name "DIFF9_N") (class "Default")
      (node (ref "IC1") (pin "C14") (pinfunction "DC2-_C14") (pintype "bidirectional"))
      (node (ref "X13") (pin "10") (pinfunction "S_10") (pintype "passive"))
    )
    (net (code "41") (name "DIFF9_P") (class "Default")
      (node (ref "IC1") (pin "C13") (pinfunction "DC2+_C13") (pintype "bidirectional"))
      (node (ref "X13") (pin "9") (pinfunction "S_9") (pintype "passive"))
    )
    (net (code "42") (name "DIFF10_N") (class "Default")
      (node (ref "IC1") (pin "F14") (pinfunction "DC5-_F14") (pintype "bidirectional"))
      (node (ref "X15") (pin "7") (pinfunction "S_7") (pintype "passive"))
    )
    (net (code "43") (name "DIFF10_P") (class "Default")
      (node (ref "IC1") (pin "F13") (pinfunction "DC5+_F13") (pintype "bidirectional"))
      (node (ref "X15") (pin "6") (pinfunction "S_6") (pintype "passive"))
    )
    (net (code "44") (name "DIFF11_N") (class "Default")
      (node (ref "IC1") (pin "C10") (pinfunction "DA2-_C10") (pintype "bidirectional"))
      (node (ref "X13") (pin "8") (pinfunction "S_8") (pintype "passive"))
    )
    (net (code "45") (name "DIFF11_P") (class "Default")
      (node (ref "IC1") (pin "C9") (pinfunction "DA2+_C9") (pintype "bidirectional"))
      (node (ref "X13") (pin "7") (pinfunction "S_7") (pintype "passive"))
    )
    (net (code "46") (name "DIFF12_N") (class "Default")
      (node (ref "IC1") (pin "E10") (pinfunction "DA4-_E10") (pintype "bidirectional"))
      (node (ref "X15") (pin "11") (pinfunction "S_11") (pintype "passive"))
    )
    (net (code "47") (name "DIFF12_P") (class "Default")
      (node (ref "IC1") (pin "E9") (pinfunction "DA4+_E9") (pintype "bidirectional"))
      (node (ref "X15") (pin "14") (pinfunction "S_14") (pintype "passive"))
    )
    (net (code "48") (name "DIFF13_N") (class "Default")
      (node (ref "IC1") (pin "G14") (pinfunction "DC6-_G14") (pintype "bidirectional"))
      (node (ref "X15") (pin "3") (pinfunction "S_3") (pintype "passive"))
    )
    (net (code "49") (name "DIFF13_P") (class "Default")
      (node (ref "IC1") (pin "G13") (pinfunction "DC6+_G13") (pintype "bidirectional"))
      (node (ref "X15") (pin "2") (pinfunction "S_2") (pintype "passive"))
    )
    (net (code "50") (name "DIFF14_N") (class "Default")
      (node (ref "IC1") (pin "K14") (pinfunction "DD6-_K14") (pintype "bidirectional"))
      (node (ref "X15") (pin "1") (pinfunction "S_1") (pintype "passive"))
    )
    (net (code "51") (name "DIFF14_P") (class "Default")
      (node (ref "IC1") (pin "K13") (pinfunction "DD6+_K13") (pintype "bidirectional"))
      (node (ref "X16") (pin "16") (pinfunction "S_16") (pintype "passive"))
    )
    (net (code "52") (name "DIFF15_N") (class "Default")
      (node (ref "IC1") (pin "A14") (pinfunction "DC0-_A14") (pintype "bidirectional"))
      (node (ref "X16") (pin "15") (pinfunction "S_15") (pintype "passive"))
    )
    (net (code "53") (name "DIFF15_P") (class "Default")
      (node (ref "IC1") (pin "A13") (pinfunction "DC0+_A13") (pintype "bidirectional"))
      (node (ref "X16") (pin "14") (pinfunction "S_14") (pintype "passive"))
    )
    (net (code "54") (name "DIFF16_N") (class "Default")
      (node (ref "IC1") (pin "D14") (pinfunction "DC3-_D14") (pintype "bidirectional"))
      (node (ref "X15") (pin "13") (pinfunction "S_13") (pintype "passive"))
    )
    (net (code "55") (name "DIFF16_P") (class "Default")
      (node (ref "IC1") (pin "D13") (pinfunction "DC3+_D13") (pintype "bidirectional"))
      (node (ref "X15") (pin "12") (pinfunction "S_12") (pintype "passive"))
    )
    (net (code "56") (name "DIFF17_N") (class "Default")
      (node (ref "IC1") (pin "D10") (pinfunction "DA3-_D10") (pintype "bidirectional"))
      (node (ref "X13") (pin "6") (pinfunction "S_6") (pintype "passive"))
    )
    (net (code "57") (name "DIFF17_P") (class "Default")
      (node (ref "IC1") (pin "D9") (pinfunction "DA3+_D9") (pintype "bidirectional"))
      (node (ref "X13") (pin "3") (pinfunction "S_3") (pintype "passive"))
    )
    (net (code "58") (name "DIFF18_N") (class "Default")
      (node (ref "IC1") (pin "A12") (pinfunction "DA6-_A12") (pintype "bidirectional"))
      (node (ref "X16") (pin "13") (pinfunction "S_13") (pintype "passive"))
    )
    (net (code "59") (name "DIFF18_P") (class "Default")
      (node (ref "IC1") (pin "A11") (pinfunction "DA6+_A11") (pintype "bidirectional"))
      (node (ref "X16") (pin "12") (pinfunction "S_12") (pintype "passive"))
    )
    (net (code "60") (name "DIFF19_N") (class "Default")
      (node (ref "IC1") (pin "A10") (pinfunction "DA0-_A10") (pintype "bidirectional"))
      (node (ref "X16") (pin "11") (pinfunction "S_11") (pintype "passive"))
    )
    (net (code "61") (name "DIFF19_P") (class "Default")
      (node (ref "IC1") (pin "A9") (pinfunction "DA0+_A9") (pintype "bidirectional"))
      (node (ref "X16") (pin "10") (pinfunction "S_10") (pintype "passive"))
    )
    (net (code "62") (name "DIFF20_N") (class "Default")
      (node (ref "IC1") (pin "E14") (pinfunction "DC4-_E14") (pintype "bidirectional"))
      (node (ref "X15") (pin "9") (pinfunction "S_9") (pintype "passive"))
    )
    (net (code "63") (name "DIFF20_P") (class "Default")
      (node (ref "IC1") (pin "E13") (pinfunction "DC4+_E13") (pintype "bidirectional"))
      (node (ref "X15") (pin "10") (pinfunction "S_10") (pintype "passive"))
    )
    (net (code "64") (name "DIFF21_N") (class "Default")
      (node (ref "IC1") (pin "F10") (pinfunction "DA5-_F10") (pintype "bidirectional"))
      (node (ref "X16") (pin "5") (pinfunction "S_5") (pintype "passive"))
    )
    (net (code "65") (name "DIFF21_P") (class "Default")
      (node (ref "IC1") (pin "F9") (pinfunction "DA5+_F9") (pintype "bidirectional"))
      (node (ref "X15") (pin "8") (pinfunction "S_8") (pintype "passive"))
    )
    (net (code "66") (name "DIFF22_N") (class "Default")
      (node (ref "IC1") (pin "L14") (pinfunction "DD5-_L14") (pintype "bidirectional"))
      (node (ref "X16") (pin "9") (pinfunction "S_9") (pintype "passive"))
    )
    (net (code "67") (name "DIFF22_P") (class "Default")
      (node (ref "IC1") (pin "L13") (pinfunction "DD5+_L13") (pintype "bidirectional"))
      (node (ref "X16") (pin "8") (pinfunction "S_8") (pintype "passive"))
    )
    (net (code "68") (name "DIFF23_N") (class "Default")
      (node (ref "IC1") (pin "M14") (pinfunction "DD4-_M14") (pintype "bidirectional"))
      (node (ref "X16") (pin "7") (pinfunction "S_7") (pintype "passive"))
    )
    (net (code "69") (name "DIFF23_P") (class "Default")
      (node (ref "IC1") (pin "M13") (pinfunction "DD4+_M13") (pintype "bidirectional"))
      (node (ref "X16") (pin "2") (pinfunction "S_2") (pintype "passive"))
    )
    (net (code "70") (name "DIFF24_N") (class "Default")
      (node (ref "IC1") (pin "B16") (pinfunction "DC7-_B16") (pintype "bidirectional"))
      (node (ref "X18") (pin "4") (pinfunction "S_4") (pintype "passive"))
    )
    (net (code "71") (name "DIFF24_P") (class "Default")
      (node (ref "IC1") (pin "B15") (pinfunction "DC7+_B15") (pintype "bidirectional"))
      (node (ref "X18") (pin "3") (pinfunction "S_3") (pintype "passive"))
    )
    (net (code "72") (name "DIFF25_N") (class "Default")
      (node (ref "IC1") (pin "P14") (pinfunction "DD2-_P14") (pintype "bidirectional"))
      (node (ref "X18") (pin "28") (pinfunction "S_28") (pintype "passive"))
    )
    (net (code "73") (name "DIFF25_P") (class "Default")
      (node (ref "IC1") (pin "P13") (pinfunction "DD2+_P13") (pintype "bidirectional"))
      (node (ref "X17") (pin "16") (pinfunction "S_16") (pintype "passive"))
    )
    (net (code "74") (name "DIFF26_N") (class "Default")
      (node (ref "IC1") (pin "C16") (pinfunction "DC8-_C16") (pintype "bidirectional"))
      (node (ref "X18") (pin "6") (pinfunction "S_6") (pintype "passive"))
    )
    (net (code "75") (name "DIFF26_P") (class "Default")
      (node (ref "IC1") (pin "C15") (pinfunction "DC8+_C15") (pintype "bidirectional"))
      (node (ref "X18") (pin "5") (pinfunction "S_5") (pintype "passive"))
    )
    (net (code "76") (name "DIFF27_N") (class "Default")
      (node (ref "IC1") (pin "D12") (pinfunction "DA9-_D12") (pintype "bidirectional"))
      (node (ref "X18") (pin "10") (pinfunction "S_10") (pintype "passive"))
    )
    (net (code "77") (name "DIFF27_P") (class "Default")
      (node (ref "IC1") (pin "D11") (pinfunction "DA9+_D11") (pintype "bidirectional"))
      (node (ref "X18") (pin "8") (pinfunction "S_8") (pintype "passive"))
    )
    (net (code "78") (name "DIFF28_N") (class "Default")
      (node (ref "IC1") (pin "J16") (pinfunction "DDSTR-_J16") (pintype "bidirectional"))
      (node (ref "X17") (pin "9") (pinfunction "S_9") (pintype "passive"))
    )
    (net (code "79") (name "DIFF28_P") (class "Default")
      (node (ref "IC1") (pin "J15") (pinfunction "DDSTR+_J15") (pintype "bidirectional"))
      (node (ref "X17") (pin "4") (pinfunction "S_4") (pintype "passive"))
    )
    (net (code "80") (name "DIFF29_N") (class "Default")
      (node (ref "IC1") (pin "N14") (pinfunction "DD3-_N14") (pintype "bidirectional"))
      (node (ref "X16") (pin "1") (pinfunction "S_1") (pintype "passive"))
    )
    (net (code "81") (name "DIFF29_P") (class "Default")
      (node (ref "IC1") (pin "N13") (pinfunction "DD3+_N13") (pintype "bidirectional"))
      (node (ref "X17") (pin "2") (pinfunction "S_2") (pintype "passive"))
    )
    (net (code "82") (name "DIFF30_N") (class "Default")
      (node (ref "IC1") (pin "D16") (pinfunction "DC9-_D16") (pintype "bidirectional"))
      (node (ref "X18") (pin "11") (pinfunction "S_11") (pintype "passive"))
    )
    (net (code "83") (name "DIFF30_P") (class "Default")
      (node (ref "IC1") (pin "D15") (pinfunction "DC9+_D15") (pintype "bidirectional"))
      (node (ref "X18") (pin "9") (pinfunction "S_9") (pintype "passive"))
    )
    (net (code "84") (name "DIFF31_N") (class "Default")
      (node (ref "IC1") (pin "E16") (pinfunction "DC10-_E16") (pintype "bidirectional"))
      (node (ref "X18") (pin "13") (pinfunction "S_13") (pintype "passive"))
    )
    (net (code "85") (name "DIFF31_P") (class "Default")
      (node (ref "IC1") (pin "E15") (pinfunction "DC10+_E15") (pintype "bidirectional"))
      (node (ref "X18") (pin "14") (pinfunction "S_14") (pintype "passive"))
    )
    (net (code "86") (name "DIFF32_N") (class "Default")
      (node (ref "IC1") (pin "G10") (pinfunction "DACLK-_G10") (pintype "bidirectional"))
      (node (ref "X18") (pin "15") (pinfunction "S_15") (pintype "passive"))
    )
    (net (code "87") (name "DIFF32_P") (class "Default")
      (node (ref "IC1") (pin "G9") (pinfunction "DACLK+_G9") (pintype "bidirectional"))
      (node (ref "X18") (pin "16") (pinfunction "S_16") (pintype "passive"))
    )
    (net (code "88") (name "DIFF33_N") (class "Default")
      (node (ref "IC1") (pin "H10") (pinfunction "DASTR-_H10") (pintype "bidirectional"))
      (node (ref "X18") (pin "17") (pinfunction "S_17") (pintype "passive"))
    )
    (net (code "89") (name "DIFF33_P") (class "Default")
      (node (ref "IC1") (pin "H9") (pinfunction "DASTR+_H9") (pintype "bidirectional"))
      (node (ref "X18") (pin "18") (pinfunction "S_18") (pintype "passive"))
    )
    (net (code "90") (name "DIFF34_N") (class "Default")
      (node (ref "IC1") (pin "F16") (pinfunction "DC11-_F16") (pintype "bidirectional"))
      (node (ref "X18") (pin "19") (pinfunction "S_19") (pintype "passive"))
    )
    (net (code "91") (name "DIFF34_P") (class "Default")
      (node (ref "IC1") (pin "F15") (pinfunction "DC11+_F15") (pintype "bidirectional"))
      (node (ref "X18") (pin "20") (pinfunction "S_20") (pintype "passive"))
    )
    (net (code "92") (name "DIFF35_N") (class "Default")
      (node (ref "IC1") (pin "K16") (pinfunction "DDCLK-_K16") (pintype "bidirectional"))
      (node (ref "X17") (pin "18") (pinfunction "S_18") (pintype "passive"))
    )
    (net (code "93") (name "DIFF35_P") (class "Default")
      (node (ref "IC1") (pin "K15") (pinfunction "DDCLK+_K15") (pintype "bidirectional"))
      (node (ref "X17") (pin "11") (pinfunction "S_11") (pintype "passive"))
    )
    (net (code "94") (name "DIFF36_N") (class "Default")
      (node (ref "IC1") (pin "G16") (pinfunction "DCCLK-_G16") (pintype "bidirectional"))
      (node (ref "X18") (pin "22") (pinfunction "S_22") (pintype "passive"))
    )
    (net (code "95") (name "DIFF36_P") (class "Default")
      (node (ref "IC1") (pin "G15") (pinfunction "DCCLK+_G15") (pintype "bidirectional"))
      (node (ref "X18") (pin "21") (pinfunction "S_21") (pintype "passive"))
    )
    (net (code "96") (name "DIFF37_N") (class "Default")
      (node (ref "IC1") (pin "H16") (pinfunction "DCSTR-_H16") (pintype "bidirectional"))
      (node (ref "X18") (pin "26") (pinfunction "S_26") (pintype "passive"))
    )
    (net (code "97") (name "DIFF37_P") (class "Default")
      (node (ref "IC1") (pin "H15") (pinfunction "DCSTR+_H15") (pintype "bidirectional"))
      (node (ref "X18") (pin "25") (pinfunction "S_25") (pintype "passive"))
    )
    (net (code "98") (name "DIFF38_N") (class "Default")
      (node (ref "IC1") (pin "L16") (pinfunction "DD11-_L16") (pintype "bidirectional"))
      (node (ref "X17") (pin "19") (pinfunction "S_19") (pintype "passive"))
    )
    (net (code "99") (name "DIFF38_P") (class "Default")
      (node (ref "IC1") (pin "L15") (pinfunction "DD11+_L15") (pintype "bidirectional"))
      (node (ref "X17") (pin "22") (pinfunction "S_22") (pintype "passive"))
    )
    (net (code "100") (name "DIFF39_N") (class "Default")
      (node (ref "IC1") (pin "M16") (pinfunction "DD10-_M16") (pintype "bidirectional"))
      (node (ref "X17") (pin "21") (pinfunction "S_21") (pintype "passive"))
    )
    (net (code "101") (name "DIFF39_P") (class "Default")
      (node (ref "IC1") (pin "M15") (pinfunction "DD10+_M15") (pintype "bidirectional"))
      (node (ref "X17") (pin "24") (pinfunction "S_24") (pintype "passive"))
    )
    (net (code "102") (name "DIFF40_N") (class "Default")
      (node (ref "IC1") (pin "N16") (pinfunction "DD9-_N16") (pintype "bidirectional"))
      (node (ref "X17") (pin "26") (pinfunction "S_26") (pintype "passive"))
    )
    (net (code "103") (name "DIFF40_P") (class "Default")
      (node (ref "IC1") (pin "N15") (pinfunction "DD9+_N15") (pintype "bidirectional"))
      (node (ref "X17") (pin "23") (pinfunction "S_23") (pintype "passive"))
    )
    (net (code "104") (name "DIFF41_N") (class "Default")
      (node (ref "IC1") (pin "P12") (pinfunction "DB8-_P12") (pintype "bidirectional"))
      (node (ref "X1") (pin "8") (pinfunction "S_8") (pintype "passive"))
    )
    (net (code "105") (name "DIFF41_P") (class "Default")
      (node (ref "IC1") (pin "P11") (pinfunction "DB8+_P11") (pintype "bidirectional"))
      (node (ref "X1") (pin "5") (pinfunction "S_5") (pintype "passive"))
    )
    (net (code "106") (name "DIFF42_N") (class "Default")
      (node (ref "IC1") (pin "N12") (pinfunction "DB9-_N12") (pintype "bidirectional"))
      (node (ref "X1") (pin "10") (pinfunction "S_10") (pintype "passive"))
    )
    (net (code "107") (name "DIFF42_P") (class "Default")
      (node (ref "IC1") (pin "N11") (pinfunction "DB9+_N11") (pintype "bidirectional"))
      (node (ref "X1") (pin "7") (pinfunction "S_7") (pintype "passive"))
    )
    (net (code "108") (name "DIFF43_N") (class "Default")
      (node (ref "IC1") (pin "M12") (pinfunction "DB10-_M12") (pintype "bidirectional"))
      (node (ref "X1") (pin "9") (pinfunction "S_9") (pintype "passive"))
    )
    (net (code "109") (name "DIFF43_P") (class "Default")
      (node (ref "IC1") (pin "M11") (pinfunction "DB10+_M11") (pintype "bidirectional"))
      (node (ref "X1") (pin "12") (pinfunction "S_12") (pintype "passive"))
    )
    (net (code "110") (name "DIFF44_N") (class "Default")
      (node (ref "IC1") (pin "F12") (pinfunction "DA11-_F12") (pintype "bidirectional"))
      (node (ref "X1") (pin "3") (pinfunction "S_3") (pintype "passive"))
    )
    (net (code "111") (name "DIFF44_P") (class "Default")
      (node (ref "IC1") (pin "F11") (pinfunction "DA11+_F11") (pintype "bidirectional"))
      (node (ref "X2") (pin "3") (pinfunction "S_3") (pintype "passive"))
    )
    (net (code "112") (name "DIFF45_N") (class "Default")
      (node (ref "IC1") (pin "E12") (pinfunction "DA10-_E12") (pintype "bidirectional"))
      (node (ref "X17") (pin "15") (pinfunction "S_15") (pintype "passive"))
    )
    (net (code "113") (name "DIFF45_P") (class "Default")
      (node (ref "IC1") (pin "E11") (pinfunction "DA10+_E11") (pintype "bidirectional"))
      (node (ref "X17") (pin "25") (pinfunction "S_25") (pintype "passive"))
    )
    (net (code "114") (name "DIFF46_N") (class "Default")
      (node (ref "IC1") (pin "P16") (pinfunction "DD8-_P16") (pintype "bidirectional"))
      (node (ref "X1") (pin "13") (pinfunction "S_13") (pintype "passive"))
    )
    (net (code "115") (name "DIFF46_P") (class "Default")
      (node (ref "IC1") (pin "P15") (pinfunction "DD8+_P15") (pintype "bidirectional"))
      (node (ref "X1") (pin "14") (pinfunction "S_14") (pintype "passive"))
    )
    (net (code "116") (name "DIFF47_N") (class "Default")
      (node (ref "IC1") (pin "T14") (pinfunction "DD0-_T14") (pintype "bidirectional"))
      (node (ref "X2") (pin "11") (pinfunction "S_11") (pintype "passive"))
    )
    (net (code "117") (name "DIFF47_P") (class "Default")
      (node (ref "IC1") (pin "T13") (pinfunction "DD0+_T13") (pintype "bidirectional"))
      (node (ref "X2") (pin "12") (pinfunction "S_12") (pintype "passive"))
    )
    (net (code "118") (name "DIFF48_N") (class "Default")
      (node (ref "IC1") (pin "T12") (pinfunction "DB6-_T12") (pintype "bidirectional"))
      (node (ref "X2") (pin "13") (pinfunction "S_13") (pintype "passive"))
    )
    (net (code "119") (name "DIFF48_P") (class "Default")
      (node (ref "IC1") (pin "T11") (pinfunction "DB6+_T11") (pintype "bidirectional"))
      (node (ref "X2") (pin "14") (pinfunction "S_14") (pintype "passive"))
    )
    (net (code "120") (name "DIFF49_N") (class "Default")
      (node (ref "IC1") (pin "L12") (pinfunction "DB11-_L12") (pintype "bidirectional"))
      (node (ref "X2") (pin "6") (pinfunction "S_6") (pintype "passive"))
    )
    (net (code "121") (name "DIFF49_P") (class "Default")
      (node (ref "IC1") (pin "L11") (pinfunction "DB11+_L11") (pintype "bidirectional"))
      (node (ref "X2") (pin "5") (pinfunction "S_5") (pintype "passive"))
    )
    (net (code "122") (name "DIFF50_N") (class "Default")
      (node (ref "IC1") (pin "T10") (pinfunction "DB0-_T10") (pintype "bidirectional"))
      (node (ref "X14") (pin "26") (pinfunction "S_26") (pintype "passive"))
    )
    (net (code "123") (name "DIFF50_P") (class "Default")
      (node (ref "IC1") (pin "T9") (pinfunction "DB0+_T9") (pintype "bidirectional"))
      (node (ref "X14") (pin "24") (pinfunction "S_24") (pintype "passive"))
    )
    (net (code "124") (name "DIFF51_N") (class "Default")
      (node (ref "IC1") (pin "R12") (pinfunction "DB7-_R12") (pintype "bidirectional"))
      (node (ref "X14") (pin "13") (pinfunction "S_13") (pintype "passive"))
    )
    (net (code "125") (name "DIFF51_P") (class "Default")
      (node (ref "IC1") (pin "R11") (pinfunction "DB7+_R11") (pintype "bidirectional"))
      (node (ref "X14") (pin "14") (pinfunction "S_14") (pintype "passive"))
    )
    (net (code "126") (name "DIFF52_N") (class "Default")
      (node (ref "IC1") (pin "P10") (pinfunction "DB2-_P10") (pintype "bidirectional"))
      (node (ref "X14") (pin "5") (pinfunction "S_5") (pintype "passive"))
    )
    (net (code "127") (name "DIFF52_P") (class "Default")
      (node (ref "IC1") (pin "P9") (pinfunction "DB2+_P9") (pintype "bidirectional"))
      (node (ref "X14") (pin "12") (pinfunction "S_12") (pintype "passive"))
    )
    (net (code "128") (name "DIFF53_N") (class "Default")
      (node (ref "IC1") (pin "N10") (pinfunction "DB3-_N10") (pintype "bidirectional"))
      (node (ref "X14") (pin "9") (pinfunction "S_9") (pintype "passive"))
    )
    (net (code "129") (name "DIFF53_P") (class "Default")
      (node (ref "IC1") (pin "N9") (pinfunction "DB3+_N9") (pintype "bidirectional"))
      (node (ref "X14") (pin "10") (pinfunction "S_10") (pintype "passive"))
    )
    (net (code "130") (name "DIFF54_N") (class "Default")
      (node (ref "IC1") (pin "R16") (pinfunction "DD7-_R16") (pintype "bidirectional"))
      (node (ref "X2") (pin "10") (pinfunction "S_10") (pintype "passive"))
    )
    (net (code "131") (name "DIFF54_P") (class "Default")
      (node (ref "IC1") (pin "R15") (pinfunction "DD7+_R15") (pintype "bidirectional"))
      (node (ref "X2") (pin "8") (pinfunction "S_8") (pintype "passive"))
    )
    (net (code "132") (name "DIFF55_N") (class "Default")
      (node (ref "IC1") (pin "R10") (pinfunction "DB1-_R10") (pintype "bidirectional"))
      (node (ref "X14") (pin "7") (pinfunction "S_7") (pintype "passive"))
    )
    (net (code "133") (name "DIFF55_P") (class "Default")
      (node (ref "IC1") (pin "R9") (pinfunction "DB1+_R9") (pintype "bidirectional"))
      (node (ref "X14") (pin "8") (pinfunction "S_8") (pintype "passive"))
    )
    (net (code "134") (name "DIFF56_N") (class "Default")
      (node (ref "IC1") (pin "R14") (pinfunction "DD1-_R14") (pintype "bidirectional"))
      (node (ref "X14") (pin "18") (pinfunction "S_18") (pintype "passive"))
    )
    (net (code "135") (name "DIFF56_P") (class "Default")
      (node (ref "IC1") (pin "R13") (pinfunction "DD1+_R13") (pintype "bidirectional"))
      (node (ref "X14") (pin "15") (pinfunction "S_15") (pintype "passive"))
    )
    (net (code "136") (name "E5") (class "Default")
      (node (ref "PINOUT2") (pin "6") (pinfunction "6_6") (pintype "bidirectional"))
      (node (ref "X14") (pin "25") (pinfunction "S_25") (pintype "passive"))
    )
    (net (code "137") (name "E6") (class "Default")
      (node (ref "PINOUT1") (pin "8") (pinfunction "8_8") (pintype "bidirectional"))
      (node (ref "X2") (pin "16") (pinfunction "S_16") (pintype "passive"))
    )
    (net (code "138") (name "E9") (class "Default")
      (node (ref "PINOUT2") (pin "7") (pinfunction "7_7") (pintype "bidirectional"))
      (node (ref "X2") (pin "1") (pinfunction "S_1") (pintype "passive"))
    )
    (net (code "139") (name "E10") (class "Default")
      (node (ref "PINOUT2") (pin "3") (pinfunction "3_3") (pintype "bidirectional"))
      (node (ref "X2") (pin "2") (pinfunction "S_2") (pintype "passive"))
    )
    (net (code "140") (name "F3") (class "Default")
      (node (ref "J8") (pin "3") (pinfunction "3_3") (pintype "passive"))
      (node (ref "R11") (pin "P$1") (pinfunction "P$1_P$1") (pintype "bidirectional"))
      (node (ref "X14") (pin "16") (pinfunction "S_16") (pintype "passive"))
    )
    (net (code "141") (name "F5") (class "Default")
      (node (ref "J10") (pin "1") (pinfunction "1_1") (pintype "passive"))
      (node (ref "R29") (pin "P$1") (pinfunction "P$1_P$1") (pintype "bidirectional"))
      (node (ref "X14") (pin "23") (pinfunction "S_23") (pintype "passive"))
    )
    (net (code "142") (name "F9") (class "Default")
      (node (ref "J8") (pin "4") (pinfunction "4_4") (pintype "passive"))
      (node (ref "R10") (pin "P$1") (pinfunction "P$1_P$1") (pintype "bidirectional"))
      (node (ref "X2") (pin "4") (pinfunction "S_4") (pintype "passive"))
    )
    (net (code "143") (name "F10_SYNCSE") (class "Default")
      (node (ref "IC1") (pin "E2") (pinfunction "SYNCSE_E2") (pintype "bidirectional"))
      (node (ref "J17") (pin "1") (pinfunction "1_1") (pintype "passive"))
      (node (ref "X1") (pin "4") (pinfunction "S_4") (pintype "passive"))
    )
    (net (code "144") (name "F13") (class "Default")
      (node (ref "J8") (pin "1") (pinfunction "1_1") (pintype "passive"))
      (node (ref "R13") (pin "P$1") (pinfunction "P$1_P$1") (pintype "bidirectional"))
      (node (ref "X17") (pin "17") (pinfunction "S_17") (pintype "passive"))
    )
    (net (code "145") (name "F14") (class "Default")
      (node (ref "J8") (pin "2") (pinfunction "2_2") (pintype "passive"))
      (node (ref "R12") (pin "P$1") (pinfunction "P$1_P$1") (pintype "bidirectional"))
      (node (ref "X17") (pin "20") (pinfunction "S_20") (pintype "passive"))
    )
    (net (code "146") (name "G5") (class "Default")
      (node (ref "J8") (pin "5") (pinfunction "5_5") (pintype "passive"))
      (node (ref "R9") (pin "P$1") (pinfunction "P$1_P$1") (pintype "bidirectional"))
      (node (ref "X14") (pin "21") (pinfunction "S_21") (pintype "passive"))
    )
    (net (code "147") (name "GND") (class "Default")
      (node (ref "B13_CLKOUT2-") (pin "2") (pinfunction "2_2") (pintype "passive"))
      (node (ref "B13_CLKOUT2-") (pin "3") (pinfunction "2_3") (pintype "passive"))
      (node (ref "B13_CLKOUT2-") (pin "4") (pinfunction "2_4") (pintype "passive"))
      (node (ref "B13_CLKOUT2-") (pin "5") (pinfunction "2_5") (pintype "passive"))
      (node (ref "C10") (pin "1") (pinfunction "1_1") (pintype "passive"))
      (node (ref "C11") (pin "1") (pinfunction "1_1") (pintype "passive"))
      (node (ref "C12") (pin "1") (pinfunction "1_1") (pintype "passive"))
      (node (ref "C13") (pin "1") (pinfunction "1_1") (pintype "passive"))
      (node (ref "C14") (pin "1") (pinfunction "1_1") (pintype "passive"))
      (node (ref "C15") (pin "2") (pinfunction "GND_1_2") (pintype "bidirectional"))
      (node (ref "C15") (pin "4") (pinfunction "GND_2_4") (pintype "bidirectional"))
      (node (ref "C16") (pin "1") (pinfunction "1_1") (pintype "passive"))
      (node (ref "C17") (pin "1") (pinfunction "1_1") (pintype "passive"))
      (node (ref "C18") (pin "1") (pinfunction "1_1") (pintype "passive"))
      (node (ref "C19") (pin "1") (pinfunction "1_1") (pintype "passive"))
      (node (ref "C20") (pin "1") (pinfunction "1_1") (pintype "passive"))
      (node (ref "C21") (pin "1") (pinfunction "1_1") (pintype "passive"))
      (node (ref "C22") (pin "1") (pinfunction "1_1") (pintype "passive"))
      (node (ref "C23") (pin "1") (pinfunction "1_1") (pintype "passive"))
      (node (ref "C24") (pin "1") (pinfunction "1_1") (pintype "passive"))
      (node (ref "C25") (pin "2") (pinfunction "GND_1_2") (pintype "bidirectional"))
      (node (ref "C25") (pin "4") (pinfunction "GND_2_4") (pintype "bidirectional"))
      (node (ref "C26") (pin "1") (pinfunction "1_1") (pintype "passive"))
      (node (ref "C27") (pin "1") (pinfunction "1_1") (pintype "passive"))
      (node (ref "C28") (pin "1") (pinfunction "1_1") (pintype "passive"))
      (node (ref "C29") (pin "1") (pinfunction "1_1") (pintype "passive"))
      (node (ref "C3") (pin "1") (pinfunction "1_1") (pintype "passive"))
      (node (ref "C30") (pin "1") (pinfunction "1_1") (pintype "passive"))
      (node (ref "C31") (pin "1") (pinfunction "1_1") (pintype "passive"))
      (node (ref "C32") (pin "1") (pinfunction "1_1") (pintype "passive"))
      (node (ref "C33") (pin "1") (pinfunction "1_1") (pintype "passive"))
      (node (ref "C35") (pin "2") (pinfunction "GND_1_2") (pintype "bidirectional"))
      (node (ref "C35") (pin "4") (pinfunction "GND_2_4") (pintype "bidirectional"))
      (node (ref "C36") (pin "1") (pinfunction "1_1") (pintype "passive"))
      (node (ref "C37") (pin "1") (pinfunction "1_1") (pintype "passive"))
      (node (ref "C38") (pin "1") (pinfunction "1_1") (pintype "passive"))
      (node (ref "C39") (pin "1") (pinfunction "1_1") (pintype "passive"))
      (node (ref "C4") (pin "1") (pinfunction "1_1") (pintype "passive"))
      (node (ref "C45") (pin "2") (pinfunction "GND_1_2") (pintype "bidirectional"))
      (node (ref "C45") (pin "4") (pinfunction "GND_2_4") (pintype "bidirectional"))
      (node (ref "C46") (pin "1") (pinfunction "1_1") (pintype "passive"))
      (node (ref "C47") (pin "1") (pinfunction "1_1") (pintype "passive"))
      (node (ref "C48") (pin "1") (pinfunction "1_1") (pintype "passive"))
      (node (ref "C49") (pin "1") (pinfunction "1_1") (pintype "passive"))
      (node (ref "C5") (pin "2") (pinfunction "GND_1_2") (pintype "bidirectional"))
      (node (ref "C5") (pin "4") (pinfunction "GND_2_4") (pintype "bidirectional"))
      (node (ref "C6") (pin "1") (pinfunction "1_1") (pintype "passive"))
      (node (ref "C7") (pin "1") (pinfunction "1_1") (pintype "passive"))
      (node (ref "C8") (pin "1") (pinfunction "1_1") (pintype "passive"))
      (node (ref "C9") (pin "1") (pinfunction "1_1") (pintype "passive"))
      (node (ref "CLK+") (pin "2") (pinfunction "2_2") (pintype "passive"))
      (node (ref "CLK+") (pin "3") (pinfunction "2_3") (pintype "passive"))
      (node (ref "CLK+") (pin "4") (pinfunction "2_4") (pintype "passive"))
      (node (ref "CLK+") (pin "5") (pinfunction "2_5") (pintype "passive"))
      (node (ref "CLK-") (pin "2") (pinfunction "2_2") (pintype "passive"))
      (node (ref "CLK-") (pin "3") (pinfunction "2_3") (pintype "passive"))
      (node (ref "CLK-") (pin "4") (pinfunction "2_4") (pintype "passive"))
      (node (ref "CLK-") (pin "5") (pinfunction "2_5") (pintype "passive"))
      (node (ref "D11_CLKOUT2+") (pin "2") (pinfunction "2_2") (pintype "passive"))
      (node (ref "D11_CLKOUT2+") (pin "3") (pinfunction "2_3") (pintype "passive"))
      (node (ref "D11_CLKOUT2+") (pin "4") (pinfunction "2_4") (pintype "passive"))
      (node (ref "D11_CLKOUT2+") (pin "5") (pinfunction "2_5") (pintype "passive"))
      (node (ref "IC1") (pin "A1") (pinfunction "AGND_1_A1") (pintype "bidirectional"))
      (node (ref "IC1") (pin "A15") (pinfunction "DGND_1_A15") (pintype "bidirectional"))
      (node (ref "IC1") (pin "A16") (pinfunction "DGND_2_A16") (pintype "bidirectional"))
      (node (ref "IC1") (pin "A2") (pinfunction "AGND_2_A2") (pintype "bidirectional"))
      (node (ref "IC1") (pin "A3") (pinfunction "AGND_3_A3") (pintype "bidirectional"))
      (node (ref "IC1") (pin "A6") (pinfunction "AGND_4_A6") (pintype "bidirectional"))
      (node (ref "IC1") (pin "A7") (pinfunction "AGND_5_A7") (pintype "bidirectional"))
      (node (ref "IC1") (pin "B3") (pinfunction "AGND_6_B3") (pintype "bidirectional"))
      (node (ref "IC1") (pin "B4") (pinfunction "AGND_7_B4") (pintype "bidirectional"))
      (node (ref "IC1") (pin "B5") (pinfunction "AGND_8_B5") (pintype "bidirectional"))
      (node (ref "IC1") (pin "B6") (pinfunction "AGND_9_B6") (pintype "bidirectional"))
      (node (ref "IC1") (pin "B7") (pinfunction "AGND_10_B7") (pintype "bidirectional"))
      (node (ref "IC1") (pin "C1") (pinfunction "AGND_11_C1") (pintype "bidirectional"))
      (node (ref "IC1") (pin "C2") (pinfunction "AGND_12_C2") (pintype "bidirectional"))
      (node (ref "IC1") (pin "C3") (pinfunction "AGND_13_C3") (pintype "bidirectional"))
      (node (ref "IC1") (pin "C4") (pinfunction "AGND_14_C4") (pintype "bidirectional"))
      (node (ref "IC1") (pin "C5") (pinfunction "AGND_15_C5") (pintype "bidirectional"))
      (node (ref "IC1") (pin "C6") (pinfunction "AGND_16_C6") (pintype "bidirectional"))
      (node (ref "IC1") (pin "C7") (pinfunction "AGND_17_C7") (pintype "bidirectional"))
      (node (ref "IC1") (pin "D3") (pinfunction "AGND_18_D3") (pintype "bidirectional"))
      (node (ref "IC1") (pin "D4") (pinfunction "AGND_19_D4") (pintype "bidirectional"))
      (node (ref "IC1") (pin "D5") (pinfunction "AGND_20_D5") (pintype "bidirectional"))
      (node (ref "IC1") (pin "D6") (pinfunction "AGND_21_D6") (pintype "bidirectional"))
      (node (ref "IC1") (pin "D7") (pinfunction "DGND_3_D7") (pintype "bidirectional"))
      (node (ref "IC1") (pin "E3") (pinfunction "AGND_22_E3") (pintype "bidirectional"))
      (node (ref "IC1") (pin "E7") (pinfunction "DGND_4_E7") (pintype "bidirectional"))
      (node (ref "IC1") (pin "F1") (pinfunction "AGND_23_F1") (pintype "bidirectional"))
      (node (ref "IC1") (pin "F2") (pinfunction "AGND_24_F2") (pintype "bidirectional"))
      (node (ref "IC1") (pin "F7") (pinfunction "DGND_5_F7") (pintype "bidirectional"))
      (node (ref "IC1") (pin "G1") (pinfunction "AGND_25_G1") (pintype "bidirectional"))
      (node (ref "IC1") (pin "G2") (pinfunction "AGND_26_G2") (pintype "bidirectional"))
      (node (ref "IC1") (pin "G7") (pinfunction "DGND_6_G7") (pintype "bidirectional"))
      (node (ref "IC1") (pin "H14") (pinfunction "DGND_9_H14") (pintype "bidirectional"))
      (node (ref "IC1") (pin "H2") (pinfunction "AGND_27_H2") (pintype "bidirectional"))
      (node (ref "IC1") (pin "H7") (pinfunction "DGND_7_H7") (pintype "bidirectional"))
      (node (ref "IC1") (pin "H8") (pinfunction "DGND_8_H8") (pintype "bidirectional"))
      (node (ref "IC1") (pin "J14") (pinfunction "DGND_12_J14") (pintype "bidirectional"))
      (node (ref "IC1") (pin "J2") (pinfunction "AGND_28_J2") (pintype "bidirectional"))
      (node (ref "IC1") (pin "J7") (pinfunction "DGND_10_J7") (pintype "bidirectional"))
      (node (ref "IC1") (pin "J8") (pinfunction "DGND_11_J8") (pintype "bidirectional"))
      (node (ref "IC1") (pin "K1") (pinfunction "AGND_29_K1") (pintype "bidirectional"))
      (node (ref "IC1") (pin "K2") (pinfunction "AGND_30_K2") (pintype "bidirectional"))
      (node (ref "IC1") (pin "K7") (pinfunction "DGND_13_K7") (pintype "bidirectional"))
      (node (ref "IC1") (pin "L1") (pinfunction "AGND_31_L1") (pintype "bidirectional"))
      (node (ref "IC1") (pin "L2") (pinfunction "AGND_32_L2") (pintype "bidirectional"))
      (node (ref "IC1") (pin "L7") (pinfunction "DGND_14_L7") (pintype "bidirectional"))
      (node (ref "IC1") (pin "M3") (pinfunction "AGND_33_M3") (pintype "bidirectional"))
      (node (ref "IC1") (pin "M7") (pinfunction "DGND_15_M7") (pintype "bidirectional"))
      (node (ref "IC1") (pin "N3") (pinfunction "AGND_34_N3") (pintype "bidirectional"))
      (node (ref "IC1") (pin "N4") (pinfunction "AGND_35_N4") (pintype "bidirectional"))
      (node (ref "IC1") (pin "N5") (pinfunction "AGND_36_N5") (pintype "bidirectional"))
      (node (ref "IC1") (pin "N6") (pinfunction "AGND_37_N6") (pintype "bidirectional"))
      (node (ref "IC1") (pin "N7") (pinfunction "DGND_16_N7") (pintype "bidirectional"))
      (node (ref "IC1") (pin "P1") (pinfunction "AGND_38_P1") (pintype "bidirectional"))
      (node (ref "IC1") (pin "P2") (pinfunction "AGND_39_P2") (pintype "bidirectional"))
      (node (ref "IC1") (pin "P3") (pinfunction "AGND_40_P3") (pintype "bidirectional"))
      (node (ref "IC1") (pin "P4") (pinfunction "AGND_41_P4") (pintype "bidirectional"))
      (node (ref "IC1") (pin "P5") (pinfunction "AGND_42_P5") (pintype "bidirectional"))
      (node (ref "IC1") (pin "P6") (pinfunction "AGND_43_P6") (pintype "bidirectional"))
      (node (ref "IC1") (pin "P7") (pinfunction "AGND_44_P7") (pintype "bidirectional"))
      (node (ref "IC1") (pin "R2") (pinfunction "AGND_45_R2") (pintype "bidirectional"))
      (node (ref "IC1") (pin "R3") (pinfunction "AGND_46_R3") (pintype "bidirectional"))
      (node (ref "IC1") (pin "R4") (pinfunction "AGND_47_R4") (pintype "bidirectional"))
      (node (ref "IC1") (pin "R5") (pinfunction "AGND_48_R5") (pintype "bidirectional"))
      (node (ref "IC1") (pin "R6") (pinfunction "AGND_49_R6") (pintype "bidirectional"))
      (node (ref "IC1") (pin "R7") (pinfunction "AGND_50_R7") (pintype "bidirectional"))
      (node (ref "IC1") (pin "T1") (pinfunction "AGND_51_T1") (pintype "bidirectional"))
      (node (ref "IC1") (pin "T15") (pinfunction "DGND_17_T15") (pintype "bidirectional"))
      (node (ref "IC1") (pin "T16") (pinfunction "DGND_18_T16") (pintype "bidirectional"))
      (node (ref "IC1") (pin "T2") (pinfunction "AGND_52_T2") (pintype "bidirectional"))
      (node (ref "IC1") (pin "T3") (pinfunction "AGND_53_T3") (pintype "bidirectional"))
      (node (ref "IC1") (pin "T6") (pinfunction "AGND_54_T6") (pintype "bidirectional"))
      (node (ref "IC1") (pin "T7") (pinfunction "AGND_55_T7") (pintype "bidirectional"))
      (node (ref "IC2") (pin "10") (pinfunction "GND_10") (pintype "bidirectional"))
      (node (ref "IC2") (pin "8") (pinfunction "DIR4_8") (pintype "bidirectional"))
      (node (ref "IC2") (pin "9") (pinfunction "~{OE}_9") (pintype "bidirectional"))
      (node (ref "INA+") (pin "2") (pinfunction "2_2") (pintype "passive"))
      (node (ref "INA+") (pin "3") (pinfunction "2_3") (pintype "passive"))
      (node (ref "INA+") (pin "4") (pinfunction "2_4") (pintype "passive"))
      (node (ref "INA+") (pin "5") (pinfunction "2_5") (pintype "passive"))
      (node (ref "INA-") (pin "2") (pinfunction "2_2") (pintype "passive"))
      (node (ref "INA-") (pin "3") (pinfunction "2_3") (pintype "passive"))
      (node (ref "INA-") (pin "4") (pinfunction "2_4") (pintype "passive"))
      (node (ref "INA-") (pin "5") (pinfunction "2_5") (pintype "passive"))
      (node (ref "INB+") (pin "2") (pinfunction "2_2") (pintype "passive"))
      (node (ref "INB+") (pin "3") (pinfunction "2_3") (pintype "passive"))
      (node (ref "INB+") (pin "4") (pinfunction "2_4") (pintype "passive"))
      (node (ref "INB+") (pin "5") (pinfunction "2_5") (pintype "passive"))
      (node (ref "INB-") (pin "2") (pinfunction "2_2") (pintype "passive"))
      (node (ref "INB-") (pin "3") (pinfunction "2_3") (pintype "passive"))
      (node (ref "INB-") (pin "4") (pinfunction "2_4") (pintype "passive"))
      (node (ref "INB-") (pin "5") (pinfunction "2_5") (pintype "passive"))
      (node (ref "J17") (pin "3") (pinfunction "3_3") (pintype "passive"))
      (node (ref "J17") (pin "7") (pinfunction "7_7") (pintype "passive"))
      (node (ref "J17") (pin "8") (pinfunction "8_8") (pintype "passive"))
      (node (ref "J2") (pin "5") (pinfunction "5_5") (pintype "passive"))
      (node (ref "J2") (pin "6") (pinfunction "6_6") (pintype "passive"))
      (node (ref "J2") (pin "7") (pinfunction "7_7") (pintype "passive"))
      (node (ref "J2") (pin "8") (pinfunction "8_8") (pintype "passive"))
      (node (ref "J4") (pin "2") (pinfunction "2_2") (pintype "passive"))
      (node (ref "J4") (pin "8") (pinfunction "8_8") (pintype "passive"))
      (node (ref "J5") (pin "1") (pinfunction "1_1") (pintype "passive"))
      (node (ref "J5") (pin "4") (pinfunction "4_4") (pintype "passive"))
      (node (ref "J5") (pin "6") (pinfunction "6_6") (pintype "passive"))
      (node (ref "J5") (pin "8") (pinfunction "8_8") (pintype "passive"))
      (node (ref "J6") (pin "1") (pinfunction "1_1") (pintype "passive"))
      (node (ref "J6") (pin "4") (pinfunction "4_4") (pintype "passive"))
      (node (ref "J6") (pin "5") (pinfunction "5_5") (pintype "passive"))
      (node (ref "J6") (pin "8") (pinfunction "8_8") (pintype "passive"))
      (node (ref "J7") (pin "3") (pinfunction "3_3") (pintype "passive"))
      (node (ref "J7") (pin "6") (pinfunction "6_6") (pintype "passive"))
      (node (ref "LED1") (pin "C") (pinfunction "C_C") (pintype "passive"))
      (node (ref "LED17") (pin "C") (pinfunction "C_C") (pintype "passive"))
      (node (ref "LED18") (pin "C") (pinfunction "C_C") (pintype "passive"))
      (node (ref "LED19") (pin "C") (pinfunction "C_C") (pintype "passive"))
      (node (ref "LED2") (pin "C") (pinfunction "C_C") (pintype "passive"))
      (node (ref "LED20") (pin "C") (pinfunction "C_C") (pintype "passive"))
      (node (ref "LED21") (pin "C") (pinfunction "C_C") (pintype "passive"))
      (node (ref "LED22") (pin "C") (pinfunction "C_C") (pintype "passive"))
      (node (ref "LED23") (pin "C") (pinfunction "C_C") (pintype "passive"))
      (node (ref "LED24") (pin "C") (pinfunction "C_C") (pintype "passive"))
      (node (ref "LED25") (pin "C") (pinfunction "C_C") (pintype "passive"))
      (node (ref "LED26") (pin "C") (pinfunction "C_C") (pintype "passive"))
      (node (ref "LED27") (pin "C") (pinfunction "C_C") (pintype "passive"))
      (node (ref "LED28") (pin "C") (pinfunction "C_C") (pintype "passive"))
      (node (ref "LED29") (pin "C") (pinfunction "C_C") (pintype "passive"))
      (node (ref "LED3") (pin "C") (pinfunction "C_C") (pintype "passive"))
      (node (ref "LED30") (pin "C") (pinfunction "C_C") (pintype "passive"))
      (node (ref "LED31") (pin "C") (pinfunction "C_C") (pintype "passive"))
      (node (ref "LED32") (pin "C") (pinfunction "C_C") (pintype "passive"))
      (node (ref "LED33") (pin "C") (pinfunction "C_C") (pintype "passive"))
      (node (ref "LED34") (pin "C") (pinfunction "C_C") (pintype "passive"))
      (node (ref "LED35") (pin "C") (pinfunction "C_C") (pintype "passive"))
      (node (ref "LED36") (pin "C") (pinfunction "C_C") (pintype "passive"))
      (node (ref "LED37") (pin "C") (pinfunction "C_C") (pintype "passive"))
      (node (ref "LED38") (pin "C") (pinfunction "C_C") (pintype "passive"))
      (node (ref "LED39") (pin "C") (pinfunction "C_C") (pintype "passive"))
      (node (ref "LED4") (pin "C") (pinfunction "C_C") (pintype "passive"))
      (node (ref "LED40") (pin "C") (pinfunction "C_C") (pintype "passive"))
      (node (ref "LED41") (pin "C") (pinfunction "C_C") (pintype "passive"))
      (node (ref "LED42") (pin "C") (pinfunction "C_C") (pintype "passive"))
      (node (ref "LED43") (pin "C") (pinfunction "C_C") (pintype "passive"))
      (node (ref "LED44") (pin "C") (pinfunction "C_C") (pintype "passive"))
      (node (ref "LED45") (pin "C") (pinfunction "C_C") (pintype "passive"))
      (node (ref "LED46") (pin "C") (pinfunction "C_C") (pintype "passive"))
      (node (ref "LED47") (pin "C") (pinfunction "C_C") (pintype "passive"))
      (node (ref "LED48") (pin "C") (pinfunction "C_C") (pintype "passive"))
      (node (ref "LED5") (pin "C") (pinfunction "C_C") (pintype "passive"))
      (node (ref "LED6") (pin "C") (pinfunction "C_C") (pintype "passive"))
      (node (ref "LED7") (pin "C") (pinfunction "C_C") (pintype "passive"))
      (node (ref "LED8") (pin "C") (pinfunction "C_C") (pintype "passive"))
      (node (ref "PINOUT1") (pin "1") (pinfunction "1_1") (pintype "bidirectional"))
      (node (ref "PINOUT2") (pin "1") (pinfunction "1_1") (pintype "bidirectional"))
      (node (ref "R4_CLKOUT+") (pin "2") (pinfunction "2_2") (pintype "passive"))
      (node (ref "R4_CLKOUT+") (pin "3") (pinfunction "2_3") (pintype "passive"))
      (node (ref "R4_CLKOUT+") (pin "4") (pinfunction "2_4") (pintype "passive"))
      (node (ref "R4_CLKOUT+") (pin "5") (pinfunction "2_5") (pintype "passive"))
      (node (ref "T4_CLKOUT-") (pin "2") (pinfunction "2_2") (pintype "passive"))
      (node (ref "T4_CLKOUT-") (pin "3") (pinfunction "2_3") (pintype "passive"))
      (node (ref "T4_CLKOUT-") (pin "4") (pinfunction "2_4") (pintype "passive"))
      (node (ref "T4_CLKOUT-") (pin "5") (pinfunction "2_5") (pintype "passive"))
      (node (ref "X13") (pin "2") (pinfunction "S_2") (pintype "passive"))
      (node (ref "X13") (pin "24") (pinfunction "S_24") (pintype "passive"))
      (node (ref "X18") (pin "1") (pinfunction "S_1") (pintype "passive"))
      (node (ref "X18") (pin "23") (pinfunction "S_23") (pintype "passive"))
    )
    (net (code "148") (name "INA_N") (class "Default")
      (node (ref "IC1") (pin "A5") (pinfunction "INA-_A5") (pintype "bidirectional"))
      (node (ref "INA-") (pin "1") (pinfunction "1_1") (pintype "passive"))
    )
    (net (code "149") (name "INA_P") (class "Default")
      (node (ref "IC1") (pin "A4") (pinfunction "INA+_A4") (pintype "bidirectional"))
      (node (ref "INA+") (pin "1") (pinfunction "1_1") (pintype "passive"))
    )
    (net (code "150") (name "INB_N") (class "Default")
      (node (ref "IC1") (pin "T5") (pinfunction "INB-_T5") (pintype "bidirectional"))
      (node (ref "INB-") (pin "1") (pinfunction "1_1") (pintype "passive"))
    )
    (net (code "151") (name "INB_P") (class "Default")
      (node (ref "IC1") (pin "T4") (pinfunction "INB+_T4") (pintype "bidirectional"))
      (node (ref "INB+") (pin "1") (pinfunction "1_1") (pintype "passive"))
    )
    (net (code "152") (name "J6") (class "Default")
      (node (ref "J8") (pin "8") (pinfunction "8_8") (pintype "passive"))
      (node (ref "R6") (pin "P$1") (pinfunction "P$1_P$1") (pintype "bidirectional"))
      (node (ref "X14") (pin "22") (pinfunction "S_22") (pintype "passive"))
    )
    (net (code "153") (name "J11") (class "Default")
      (node (ref "J8") (pin "6") (pinfunction "6_6") (pintype "passive"))
      (node (ref "R8") (pin "P$1") (pinfunction "P$1_P$1") (pintype "bidirectional"))
      (node (ref "X17") (pin "13") (pinfunction "S_13") (pintype "passive"))
    )
    (net (code "154") (name "J13") (class "Default")
      (node (ref "J8") (pin "7") (pinfunction "7_7") (pintype "passive"))
      (node (ref "R7") (pin "P$1") (pinfunction "P$1_P$1") (pintype "bidirectional"))
      (node (ref "X17") (pin "10") (pinfunction "S_10") (pintype "passive"))
    )
    (net (code "155") (name "K5") (class "Default")
      (node (ref "J10") (pin "4") (pinfunction "4_4") (pintype "passive"))
      (node (ref "R26") (pin "P$1") (pinfunction "P$1_P$1") (pintype "bidirectional"))
      (node (ref "X14") (pin "19") (pinfunction "S_19") (pintype "passive"))
    )
    (net (code "156") (name "K11") (class "Default")
      (node (ref "J10") (pin "2") (pinfunction "2_2") (pintype "passive"))
      (node (ref "R28") (pin "P$1") (pinfunction "P$1_P$1") (pintype "bidirectional"))
      (node (ref "X17") (pin "14") (pinfunction "S_14") (pintype "passive"))
    )
    (net (code "157") (name "K12") (class "Default")
      (node (ref "J10") (pin "3") (pinfunction "3_3") (pintype "passive"))
      (node (ref "R27") (pin "P$1") (pinfunction "P$1_P$1") (pintype "bidirectional"))
      (node (ref "X17") (pin "12") (pinfunction "S_12") (pintype "passive"))
    )
    (net (code "158") (name "L3") (class "Default")
      (node (ref "J10") (pin "8") (pinfunction "8_8") (pintype "passive"))
      (node (ref "R22") (pin "P$1") (pinfunction "P$1_P$1") (pintype "bidirectional"))
      (node (ref "X13") (pin "11") (pinfunction "S_11") (pintype "passive"))
    )
    (net (code "159") (name "L4") (class "Default")
      (node (ref "J11") (pin "1") (pinfunction "1_1") (pintype "passive"))
      (node (ref "R37") (pin "P$1") (pinfunction "P$1_P$1") (pintype "bidirectional"))
      (node (ref "X13") (pin "12") (pinfunction "S_12") (pintype "passive"))
    )
    (net (code "160") (name "L7") (class "Default")
      (node (ref "J11") (pin "2") (pinfunction "2_2") (pintype "passive"))
      (node (ref "R36") (pin "P$1") (pinfunction "P$1_P$1") (pintype "bidirectional"))
      (node (ref "X15") (pin "15") (pinfunction "S_15") (pintype "passive"))
    )
    (net (code "161") (name "L12") (class "Default")
      (node (ref "J10") (pin "5") (pinfunction "5_5") (pintype "passive"))
      (node (ref "R25") (pin "P$1") (pinfunction "P$1_P$1") (pintype "bidirectional"))
      (node (ref "X17") (pin "8") (pinfunction "S_8") (pintype "passive"))
    )
    (net (code "162") (name "L13") (class "Default")
      (node (ref "J10") (pin "6") (pinfunction "6_6") (pintype "passive"))
      (node (ref "R24") (pin "P$1") (pinfunction "P$1_P$1") (pintype "bidirectional"))
      (node (ref "X17") (pin "6") (pinfunction "S_6") (pintype "passive"))
    )
    (net (code "163") (name "L14") (class "Default")
      (node (ref "J10") (pin "7") (pinfunction "7_7") (pintype "passive"))
      (node (ref "R23") (pin "P$1") (pinfunction "P$1_P$1") (pintype "bidirectional"))
      (node (ref "X17") (pin "7") (pinfunction "S_7") (pintype "passive"))
    )
    (net (code "164") (name "M6") (class "Default")
      (node (ref "J11") (pin "5") (pinfunction "5_5") (pintype "passive"))
      (node (ref "R33") (pin "P$1") (pinfunction "P$1_P$1") (pintype "bidirectional"))
      (node (ref "X15") (pin "16") (pinfunction "S_16") (pintype "passive"))
    )
    (net (code "165") (name "M10") (class "Default")
      (node (ref "J11") (pin "3") (pinfunction "3_3") (pintype "passive"))
      (node (ref "R35") (pin "P$1") (pinfunction "P$1_P$1") (pintype "bidirectional"))
      (node (ref "X18") (pin "27") (pinfunction "S_27") (pintype "passive"))
    )
    (net (code "166") (name "M12") (class "Default")
      (node (ref "J11") (pin "4") (pinfunction "4_4") (pintype "passive"))
      (node (ref "R34") (pin "P$1") (pinfunction "P$1_P$1") (pintype "bidirectional"))
      (node (ref "X17") (pin "5") (pinfunction "S_5") (pintype "passive"))
    )
    (net (code "167") (name "N11") (class "Default")
      (node (ref "J11") (pin "6") (pinfunction "6_6") (pintype "passive"))
      (node (ref "R32") (pin "P$1") (pinfunction "P$1_P$1") (pintype "bidirectional"))
      (node (ref "X16") (pin "3") (pinfunction "S_3") (pintype "passive"))
    )
    (net (code "168") (name "N13") (class "Default")
      (node (ref "J11") (pin "7") (pinfunction "7_7") (pintype "passive"))
      (node (ref "R31") (pin "P$1") (pinfunction "P$1_P$1") (pintype "bidirectional"))
      (node (ref "X17") (pin "1") (pinfunction "S_1") (pintype "passive"))
    )
    (net (code "169") (name "N14") (class "Default")
      (node (ref "J11") (pin "8") (pinfunction "8_8") (pintype "passive"))
      (node (ref "R30") (pin "P$1") (pinfunction "P$1_P$1") (pintype "bidirectional"))
      (node (ref "X17") (pin "3") (pinfunction "S_3") (pintype "passive"))
    )
    (net (code "170") (name "Net-(LED1-PadA)") (class "Default")
      (node (ref "LED1") (pin "A") (pinfunction "A_A") (pintype "passive"))
      (node (ref "R13") (pin "P$2") (pinfunction "P$2_P$2") (pintype "bidirectional"))
    )
    (net (code "171") (name "Net-(LED2-PadA)") (class "Default")
      (node (ref "LED2") (pin "A") (pinfunction "A_A") (pintype "passive"))
      (node (ref "R12") (pin "P$2") (pinfunction "P$2_P$2") (pintype "bidirectional"))
    )
    (net (code "172") (name "Net-(LED3-PadA)") (class "Default")
      (node (ref "LED3") (pin "A") (pinfunction "A_A") (pintype "passive"))
      (node (ref "R11") (pin "P$2") (pinfunction "P$2_P$2") (pintype "bidirectional"))
    )
    (net (code "173") (name "Net-(LED4-PadA)") (class "Default")
      (node (ref "LED4") (pin "A") (pinfunction "A_A") (pintype "passive"))
      (node (ref "R10") (pin "P$2") (pinfunction "P$2_P$2") (pintype "bidirectional"))
    )
    (net (code "174") (name "Net-(LED5-PadA)") (class "Default")
      (node (ref "LED5") (pin "A") (pinfunction "A_A") (pintype "passive"))
      (node (ref "R9") (pin "P$2") (pinfunction "P$2_P$2") (pintype "bidirectional"))
    )
    (net (code "175") (name "Net-(LED6-PadA)") (class "Default")
      (node (ref "LED6") (pin "A") (pinfunction "A_A") (pintype "passive"))
      (node (ref "R8") (pin "P$2") (pinfunction "P$2_P$2") (pintype "bidirectional"))
    )
    (net (code "176") (name "Net-(LED7-PadA)") (class "Default")
      (node (ref "LED7") (pin "A") (pinfunction "A_A") (pintype "passive"))
      (node (ref "R7") (pin "P$2") (pinfunction "P$2_P$2") (pintype "bidirectional"))
    )
    (net (code "177") (name "Net-(LED8-PadA)") (class "Default")
      (node (ref "LED8") (pin "A") (pinfunction "A_A") (pintype "passive"))
      (node (ref "R6") (pin "P$2") (pinfunction "P$2_P$2") (pintype "bidirectional"))
    )
    (net (code "178") (name "Net-(LED17-PadA)") (class "Default")
      (node (ref "LED17") (pin "A") (pinfunction "A_A") (pintype "passive"))
      (node (ref "R29") (pin "P$2") (pinfunction "P$2_P$2") (pintype "bidirectional"))
    )
    (net (code "179") (name "Net-(LED18-PadA)") (class "Default")
      (node (ref "LED18") (pin "A") (pinfunction "A_A") (pintype "passive"))
      (node (ref "R28") (pin "P$2") (pinfunction "P$2_P$2") (pintype "bidirectional"))
    )
    (net (code "180") (name "Net-(LED19-PadA)") (class "Default")
      (node (ref "LED19") (pin "A") (pinfunction "A_A") (pintype "passive"))
      (node (ref "R27") (pin "P$2") (pinfunction "P$2_P$2") (pintype "bidirectional"))
    )
    (net (code "181") (name "Net-(LED20-PadA)") (class "Default")
      (node (ref "LED20") (pin "A") (pinfunction "A_A") (pintype "passive"))
      (node (ref "R26") (pin "P$2") (pinfunction "P$2_P$2") (pintype "bidirectional"))
    )
    (net (code "182") (name "Net-(LED21-PadA)") (class "Default")
      (node (ref "LED21") (pin "A") (pinfunction "A_A") (pintype "passive"))
      (node (ref "R25") (pin "P$2") (pinfunction "P$2_P$2") (pintype "bidirectional"))
    )
    (net (code "183") (name "Net-(LED22-PadA)") (class "Default")
      (node (ref "LED22") (pin "A") (pinfunction "A_A") (pintype "passive"))
      (node (ref "R24") (pin "P$2") (pinfunction "P$2_P$2") (pintype "bidirectional"))
    )
    (net (code "184") (name "Net-(LED23-PadA)") (class "Default")
      (node (ref "LED23") (pin "A") (pinfunction "A_A") (pintype "passive"))
      (node (ref "R23") (pin "P$2") (pinfunction "P$2_P$2") (pintype "bidirectional"))
    )
    (net (code "185") (name "Net-(LED24-PadA)") (class "Default")
      (node (ref "LED24") (pin "A") (pinfunction "A_A") (pintype "passive"))
      (node (ref "R22") (pin "P$2") (pinfunction "P$2_P$2") (pintype "bidirectional"))
    )
    (net (code "186") (name "Net-(LED25-PadA)") (class "Default")
      (node (ref "LED25") (pin "A") (pinfunction "A_A") (pintype "passive"))
      (node (ref "R37") (pin "P$2") (pinfunction "P$2_P$2") (pintype "bidirectional"))
    )
    (net (code "187") (name "Net-(LED26-PadA)") (class "Default")
      (node (ref "LED26") (pin "A") (pinfunction "A_A") (pintype "passive"))
      (node (ref "R36") (pin "P$2") (pinfunction "P$2_P$2") (pintype "bidirectional"))
    )
    (net (code "188") (name "Net-(LED27-PadA)") (class "Default")
      (node (ref "LED27") (pin "A") (pinfunction "A_A") (pintype "passive"))
      (node (ref "R35") (pin "P$2") (pinfunction "P$2_P$2") (pintype "bidirectional"))
    )
    (net (code "189") (name "Net-(LED28-PadA)") (class "Default")
      (node (ref "LED28") (pin "A") (pinfunction "A_A") (pintype "passive"))
      (node (ref "R34") (pin "P$2") (pinfunction "P$2_P$2") (pintype "bidirectional"))
    )
    (net (code "190") (name "Net-(LED29-PadA)") (class "Default")
      (node (ref "LED29") (pin "A") (pinfunction "A_A") (pintype "passive"))
      (node (ref "R33") (pin "P$2") (pinfunction "P$2_P$2") (pintype "bidirectional"))
    )
    (net (code "191") (name "Net-(LED30-PadA)") (class "Default")
      (node (ref "LED30") (pin "A") (pinfunction "A_A") (pintype "passive"))
      (node (ref "R32") (pin "P$2") (pinfunction "P$2_P$2") (pintype "bidirectional"))
    )
    (net (code "192") (name "Net-(LED31-PadA)") (class "Default")
      (node (ref "LED31") (pin "A") (pinfunction "A_A") (pintype "passive"))
      (node (ref "R31") (pin "P$2") (pinfunction "P$2_P$2") (pintype "bidirectional"))
    )
    (net (code "193") (name "Net-(LED32-PadA)") (class "Default")
      (node (ref "LED32") (pin "A") (pinfunction "A_A") (pintype "passive"))
      (node (ref "R30") (pin "P$2") (pinfunction "P$2_P$2") (pintype "bidirectional"))
    )
    (net (code "194") (name "Net-(LED33-PadA)") (class "Default")
      (node (ref "LED33") (pin "A") (pinfunction "A_A") (pintype "passive"))
      (node (ref "R45") (pin "P$2") (pinfunction "P$2_P$2") (pintype "bidirectional"))
    )
    (net (code "195") (name "Net-(LED34-PadA)") (class "Default")
      (node (ref "LED34") (pin "A") (pinfunction "A_A") (pintype "passive"))
      (node (ref "R44") (pin "P$2") (pinfunction "P$2_P$2") (pintype "bidirectional"))
    )
    (net (code "196") (name "Net-(LED35-PadA)") (class "Default")
      (node (ref "LED35") (pin "A") (pinfunction "A_A") (pintype "passive"))
      (node (ref "R43") (pin "P$2") (pinfunction "P$2_P$2") (pintype "bidirectional"))
    )
    (net (code "197") (name "Net-(LED36-PadA)") (class "Default")
      (node (ref "LED36") (pin "A") (pinfunction "A_A") (pintype "passive"))
      (node (ref "R42") (pin "P$2") (pinfunction "P$2_P$2") (pintype "bidirectional"))
    )
    (net (code "198") (name "Net-(LED37-PadA)") (class "Default")
      (node (ref "LED37") (pin "A") (pinfunction "A_A") (pintype "passive"))
      (node (ref "R41") (pin "P$2") (pinfunction "P$2_P$2") (pintype "bidirectional"))
    )
    (net (code "199") (name "Net-(LED38-PadA)") (class "Default")
      (node (ref "LED38") (pin "A") (pinfunction "A_A") (pintype "passive"))
      (node (ref "R40") (pin "P$2") (pinfunction "P$2_P$2") (pintype "bidirectional"))
    )
    (net (code "200") (name "Net-(LED39-PadA)") (class "Default")
      (node (ref "LED39") (pin "A") (pinfunction "A_A") (pintype "passive"))
      (node (ref "R39") (pin "P$2") (pinfunction "P$2_P$2") (pintype "bidirectional"))
    )
    (net (code "201") (name "Net-(LED40-PadA)") (class "Default")
      (node (ref "LED40") (pin "A") (pinfunction "A_A") (pintype "passive"))
      (node (ref "R38") (pin "P$2") (pinfunction "P$2_P$2") (pintype "bidirectional"))
    )
    (net (code "202") (name "Net-(LED41-PadA)") (class "Default")
      (node (ref "LED41") (pin "A") (pinfunction "A_A") (pintype "passive"))
      (node (ref "R53") (pin "P$2") (pinfunction "P$2_P$2") (pintype "bidirectional"))
    )
    (net (code "203") (name "Net-(LED42-PadA)") (class "Default")
      (node (ref "LED42") (pin "A") (pinfunction "A_A") (pintype "passive"))
      (node (ref "R52") (pin "P$2") (pinfunction "P$2_P$2") (pintype "bidirectional"))
    )
    (net (code "204") (name "Net-(LED43-PadA)") (class "Default")
      (node (ref "LED43") (pin "A") (pinfunction "A_A") (pintype "passive"))
      (node (ref "R51") (pin "P$2") (pinfunction "P$2_P$2") (pintype "bidirectional"))
    )
    (net (code "205") (name "Net-(LED44-PadA)") (class "Default")
      (node (ref "LED44") (pin "A") (pinfunction "A_A") (pintype "passive"))
      (node (ref "R50") (pin "P$2") (pinfunction "P$2_P$2") (pintype "bidirectional"))
    )
    (net (code "206") (name "Net-(LED45-PadA)") (class "Default")
      (node (ref "LED45") (pin "A") (pinfunction "A_A") (pintype "passive"))
      (node (ref "R49") (pin "P$2") (pinfunction "P$2_P$2") (pintype "bidirectional"))
    )
    (net (code "207") (name "Net-(LED46-PadA)") (class "Default")
      (node (ref "LED46") (pin "A") (pinfunction "A_A") (pintype "passive"))
      (node (ref "R48") (pin "P$2") (pinfunction "P$2_P$2") (pintype "bidirectional"))
    )
    (net (code "208") (name "Net-(LED47-PadA)") (class "Default")
      (node (ref "LED47") (pin "A") (pinfunction "A_A") (pintype "passive"))
      (node (ref "R47") (pin "P$2") (pinfunction "P$2_P$2") (pintype "bidirectional"))
    )
    (net (code "209") (name "Net-(LED48-PadA)") (class "Default")
      (node (ref "LED48") (pin "A") (pinfunction "A_A") (pintype "passive"))
      (node (ref "R46") (pin "P$2") (pinfunction "P$2_P$2") (pintype "bidirectional"))
    )
    (net (code "210") (name "ORA0") (class "Default")
      (node (ref "IC1") (pin "B8") (pinfunction "ORA0_B8") (pintype "bidirectional"))
      (node (ref "J12") (pin "5") (pinfunction "5_5") (pintype "passive"))
      (node (ref "J16") (pin "5") (pinfunction "5_5") (pintype "passive"))
      (node (ref "R41") (pin "P$1") (pinfunction "P$1_P$1") (pintype "bidirectional"))
    )
    (net (code "211") (name "ORA1") (class "Default")
      (node (ref "IC1") (pin "A8") (pinfunction "ORA1_A8") (pintype "bidirectional"))
      (node (ref "J12") (pin "6") (pinfunction "6_6") (pintype "passive"))
      (node (ref "J16") (pin "6") (pinfunction "6_6") (pintype "passive"))
      (node (ref "R40") (pin "P$1") (pinfunction "P$1_P$1") (pintype "bidirectional"))
    )
    (net (code "212") (name "ORB0") (class "Default")
      (node (ref "IC1") (pin "D8") (pinfunction "ORB0_D8") (pintype "bidirectional"))
      (node (ref "J12") (pin "7") (pinfunction "7_7") (pintype "passive"))
      (node (ref "J16") (pin "7") (pinfunction "7_7") (pintype "passive"))
      (node (ref "R39") (pin "P$1") (pinfunction "P$1_P$1") (pintype "bidirectional"))
    )
    (net (code "213") (name "ORB1") (class "Default")
      (node (ref "IC1") (pin "C8") (pinfunction "ORB1_C8") (pintype "bidirectional"))
      (node (ref "J12") (pin "8") (pinfunction "8_8") (pintype "passive"))
      (node (ref "J16") (pin "8") (pinfunction "8_8") (pintype "passive"))
      (node (ref "R38") (pin "P$1") (pinfunction "P$1_P$1") (pintype "bidirectional"))
    )
    (net (code "214") (name "P6") (class "Default")
      (node (ref "J13") (pin "3") (pinfunction "3_3") (pintype "passive"))
      (node (ref "R51") (pin "P$1") (pinfunction "P$1_P$1") (pintype "bidirectional"))
      (node (ref "X13") (pin "5") (pinfunction "S_5") (pintype "passive"))
    )
    (net (code "215") (name "P9") (class "Default")
      (node (ref "J13") (pin "4") (pinfunction "4_4") (pintype "passive"))
      (node (ref "R50") (pin "P$1") (pinfunction "P$1_P$1") (pintype "bidirectional"))
      (node (ref "X16") (pin "6") (pinfunction "S_6") (pintype "passive"))
    )
    (net (code "216") (name "P11") (class "Default")
      (node (ref "J13") (pin "1") (pinfunction "1_1") (pintype "passive"))
      (node (ref "R53") (pin "P$1") (pinfunction "P$1_P$1") (pintype "bidirectional"))
      (node (ref "X16") (pin "4") (pinfunction "S_4") (pintype "passive"))
    )
    (net (code "217") (name "P15") (class "Default")
      (node (ref "J13") (pin "2") (pinfunction "2_2") (pintype "passive"))
      (node (ref "R52") (pin "P$1") (pinfunction "P$1_P$1") (pintype "bidirectional"))
      (node (ref "X18") (pin "12") (pinfunction "S_12") (pintype "passive"))
    )
    (net (code "218") (name "PD") (class "Default")
      (node (ref "IC1") (pin "R1") (pinfunction "PD_R1") (pintype "bidirectional"))
      (node (ref "J17") (pin "6") (pinfunction "6_6") (pintype "passive"))
    )
    (net (code "219") (name "R1") (class "Default")
      (node (ref "J13") (pin "5") (pinfunction "5_5") (pintype "passive"))
      (node (ref "R49") (pin "P$1") (pinfunction "P$1_P$1") (pintype "bidirectional"))
      (node (ref "X13") (pin "13") (pinfunction "S_13") (pintype "passive"))
    )
    (net (code "220") (name "R4_CLKOUT1P") (class "Default")
      (node (ref "R4_CLKOUT+") (pin "1") (pinfunction "1_1") (pintype "passive"))
      (node (ref "X15") (pin "4") (pinfunction "S_4") (pintype "passive"))
    )
    (net (code "221") (name "R14") (class "Default")
      (node (ref "J13") (pin "6") (pinfunction "6_6") (pintype "passive"))
      (node (ref "R48") (pin "P$1") (pinfunction "P$1_P$1") (pintype "bidirectional"))
      (node (ref "X18") (pin "7") (pinfunction "S_7") (pintype "passive"))
    )
    (net (code "222") (name "SCLK") (class "Default")
      (node (ref "IC1") (pin "T8") (pinfunction "SCLK_T8") (pintype "bidirectional"))
      (node (ref "J16") (pin "1") (pinfunction "1_1") (pintype "passive"))
      (node (ref "R1") (pin "P$2") (pinfunction "P$2_P$2") (pintype "bidirectional"))
    )
    (net (code "223") (name "SCLK3") (class "Default")
      (node (ref "IC2") (pin "3") (pinfunction "A1_3") (pintype "bidirectional"))
      (node (ref "J4") (pin "3") (pinfunction "3_3") (pintype "passive"))
    )
    (net (code "224") (name "SCLKT") (class "Default")
      (node (ref "IC2") (pin "14") (pinfunction "B1_14") (pintype "bidirectional"))
      (node (ref "R1") (pin "P$1") (pinfunction "P$1_P$1") (pintype "bidirectional"))
    )
    (net (code "225") (name "SCS") (class "Default")
      (node (ref "IC1") (pin "R8") (pinfunction "SCS_R8") (pintype "bidirectional"))
      (node (ref "J16") (pin "2") (pinfunction "2_2") (pintype "passive"))
      (node (ref "R2") (pin "P$2") (pinfunction "P$2_P$2") (pintype "bidirectional"))
    )
    (net (code "226") (name "SCS3") (class "Default")
      (node (ref "IC2") (pin "4") (pinfunction "A2_4") (pintype "bidirectional"))
      (node (ref "J4") (pin "4") (pinfunction "4_4") (pintype "passive"))
    )
    (net (code "227") (name "SCST") (class "Default")
      (node (ref "IC2") (pin "13") (pinfunction "B2_13") (pintype "bidirectional"))
      (node (ref "R2") (pin "P$1") (pinfunction "P$1_P$1") (pintype "bidirectional"))
      (node (ref "R5") (pin "P$2") (pinfunction "P$2_P$2") (pintype "bidirectional"))
    )
    (net (code "228") (name "SDI") (class "Default")
      (node (ref "IC1") (pin "P8") (pinfunction "SDI_P8") (pintype "bidirectional"))
      (node (ref "J16") (pin "3") (pinfunction "3_3") (pintype "passive"))
      (node (ref "R3") (pin "P$2") (pinfunction "P$2_P$2") (pintype "bidirectional"))
    )
    (net (code "229") (name "SDI3") (class "Default")
      (node (ref "IC2") (pin "5") (pinfunction "A3_5") (pintype "bidirectional"))
      (node (ref "J4") (pin "5") (pinfunction "5_5") (pintype "passive"))
    )
    (net (code "230") (name "SDIT") (class "Default")
      (node (ref "IC2") (pin "12") (pinfunction "B3_12") (pintype "bidirectional"))
      (node (ref "R3") (pin "P$1") (pinfunction "P$1_P$1") (pintype "bidirectional"))
    )
    (net (code "231") (name "SDO") (class "Default")
      (node (ref "IC1") (pin "N8") (pinfunction "SDO_N8") (pintype "bidirectional"))
      (node (ref "J16") (pin "4") (pinfunction "4_4") (pintype "passive"))
      (node (ref "R4") (pin "P$2") (pinfunction "P$2_P$2") (pintype "bidirectional"))
    )
    (net (code "232") (name "SDO3") (class "Default")
      (node (ref "IC2") (pin "6") (pinfunction "A4_6") (pintype "bidirectional"))
      (node (ref "J4") (pin "6") (pinfunction "6_6") (pintype "passive"))
    )
    (net (code "233") (name "SDOT") (class "Default")
      (node (ref "IC2") (pin "11") (pinfunction "B4_11") (pintype "bidirectional"))
      (node (ref "R4") (pin "P$1") (pinfunction "P$1_P$1") (pintype "bidirectional"))
    )
    (net (code "234") (name "SYSREF1") (class "Default")
      (node (ref "IC1") (pin "M1") (pinfunction "SYSREF+_M1") (pintype "bidirectional"))
      (node (ref "J7") (pin "4") (pinfunction "4_4") (pintype "passive"))
    )
    (net (code "235") (name "SYSREF2") (class "Default")
      (node (ref "IC1") (pin "N1") (pinfunction "SYSREF-_N1") (pintype "bidirectional"))
      (node (ref "J7") (pin "5") (pinfunction "5_5") (pintype "passive"))
    )
    (net (code "236") (name "T2") (class "Default")
      (node (ref "J13") (pin "7") (pinfunction "7_7") (pintype "passive"))
      (node (ref "R47") (pin "P$1") (pinfunction "P$1_P$1") (pintype "bidirectional"))
      (node (ref "X13") (pin "14") (pinfunction "S_14") (pintype "passive"))
    )
    (net (code "237") (name "T4_CLKOUT1N") (class "Default")
      (node (ref "T4_CLKOUT-") (pin "1") (pinfunction "1_1") (pintype "passive"))
      (node (ref "X15") (pin "5") (pinfunction "S_5") (pintype "passive"))
    )
    (net (code "238") (name "TDIODE1") (class "Default")
      (node (ref "IC1") (pin "M2") (pinfunction "TDIODE+_M2") (pintype "bidirectional"))
      (node (ref "J7") (pin "7") (pinfunction "7_7") (pintype "passive"))
    )
    (net (code "239") (name "TDIODE2") (class "Default")
      (node (ref "IC1") (pin "N2") (pinfunction "TDIODE-_N2") (pintype "bidirectional"))
      (node (ref "J7") (pin "8") (pinfunction "8_8") (pintype "passive"))
    )
    (net (code "240") (name "TMSTP1") (class "Default")
      (node (ref "IC1") (pin "D1") (pinfunction "TMSTP+_D1") (pintype "bidirectional"))
      (node (ref "J7") (pin "1") (pinfunction "1_1") (pintype "passive"))
    )
    (net (code "241") (name "TMSTP2") (class "Default")
      (node (ref "IC1") (pin "E1") (pinfunction "TMSTP-_E1") (pintype "bidirectional"))
      (node (ref "J7") (pin "2") (pinfunction "2_2") (pintype "passive"))
    )
    (net (code "242") (name "V11_IN") (class "Default")
      (node (ref "C35") (pin "1") (pinfunction "IN_1") (pintype "bidirectional"))
      (node (ref "C36") (pin "2") (pinfunction "2_2") (pintype "passive"))
      (node (ref "C37") (pin "2") (pinfunction "2_2") (pintype "passive"))
      (node (ref "C45") (pin "1") (pinfunction "IN_1") (pintype "bidirectional"))
      (node (ref "C46") (pin "2") (pinfunction "2_2") (pintype "passive"))
      (node (ref "C47") (pin "2") (pinfunction "2_2") (pintype "passive"))
      (node (ref "J5") (pin "3") (pinfunction "3_3") (pintype "passive"))
      (node (ref "J5") (pin "5") (pinfunction "5_5") (pintype "passive"))
    )
    (net (code "243") (name "V19_IN") (class "Default")
      (node (ref "C15") (pin "1") (pinfunction "IN_1") (pintype "bidirectional"))
      (node (ref "C16") (pin "2") (pinfunction "2_2") (pintype "passive"))
      (node (ref "C17") (pin "2") (pinfunction "2_2") (pintype "passive"))
      (node (ref "C25") (pin "1") (pinfunction "IN_1") (pintype "bidirectional"))
      (node (ref "C26") (pin "2") (pinfunction "2_2") (pintype "passive"))
      (node (ref "C27") (pin "2") (pinfunction "2_2") (pintype "passive"))
      (node (ref "J5") (pin "7") (pinfunction "7_7") (pintype "passive"))
    )
    (net (code "244") (name "VA11") (class "Default")
      (node (ref "C21") (pin "2") (pinfunction "2_2") (pintype "passive"))
      (node (ref "C22") (pin "2") (pinfunction "2_2") (pintype "passive"))
      (node (ref "C23") (pin "2") (pinfunction "2_2") (pintype "passive"))
      (node (ref "C32") (pin "2") (pinfunction "2_2") (pintype "passive"))
      (node (ref "C33") (pin "2") (pinfunction "2_2") (pintype "passive"))
      (node (ref "C35") (pin "3") (pinfunction "OUT_3") (pintype "bidirectional"))
      (node (ref "C38") (pin "2") (pinfunction "2_2") (pintype "passive"))
      (node (ref "C39") (pin "2") (pinfunction "2_2") (pintype "passive"))
      (node (ref "IC1") (pin "E4") (pinfunction "VA11_1_E4") (pintype "bidirectional"))
      (node (ref "IC1") (pin "E5") (pinfunction "VA11_2_E5") (pintype "bidirectional"))
      (node (ref "IC1") (pin "E6") (pinfunction "VA11_3_E6") (pintype "bidirectional"))
      (node (ref "IC1") (pin "F3") (pinfunction "VA11_4_F3") (pintype "bidirectional"))
      (node (ref "IC1") (pin "F4") (pinfunction "VA11_5_F4") (pintype "bidirectional"))
      (node (ref "IC1") (pin "F5") (pinfunction "VA11_6_F5") (pintype "bidirectional"))
      (node (ref "IC1") (pin "F6") (pinfunction "VA11_7_F6") (pintype "bidirectional"))
      (node (ref "IC1") (pin "L3") (pinfunction "VA11_8_L3") (pintype "bidirectional"))
      (node (ref "IC1") (pin "L4") (pinfunction "VA11_9_L4") (pintype "bidirectional"))
      (node (ref "IC1") (pin "L5") (pinfunction "VA11_10_L5") (pintype "bidirectional"))
      (node (ref "IC1") (pin "L6") (pinfunction "VA11_11_L6") (pintype "bidirectional"))
      (node (ref "IC1") (pin "M4") (pinfunction "VA11_12_M4") (pintype "bidirectional"))
      (node (ref "IC1") (pin "M5") (pinfunction "VA11_13_M5") (pintype "bidirectional"))
      (node (ref "IC1") (pin "M6") (pinfunction "VA11_14_M6") (pintype "bidirectional"))
      (node (ref "J3") (pin "1") (pinfunction "1_1") (pintype "passive"))
      (node (ref "J3") (pin "2") (pinfunction "2_2") (pintype "passive"))
      (node (ref "J3") (pin "3") (pinfunction "3_3") (pintype "passive"))
      (node (ref "J3") (pin "4") (pinfunction "4_4") (pintype "passive"))
    )
    (net (code "245") (name "VA19") (class "Default")
      (node (ref "C13") (pin "2") (pinfunction "2_2") (pintype "passive"))
      (node (ref "C14") (pin "2") (pinfunction "2_2") (pintype "passive"))
      (node (ref "C20") (pin "2") (pinfunction "2_2") (pintype "passive"))
      (node (ref "C25") (pin "3") (pinfunction "OUT_3") (pintype "bidirectional"))
      (node (ref "C28") (pin "2") (pinfunction "2_2") (pintype "passive"))
      (node (ref "C29") (pin "2") (pinfunction "2_2") (pintype "passive"))
      (node (ref "IC1") (pin "G3") (pinfunction "VA19_1_G3") (pintype "bidirectional"))
      (node (ref "IC1") (pin "G4") (pinfunction "VA19_2_G4") (pintype "bidirectional"))
      (node (ref "IC1") (pin "G5") (pinfunction "VA19_3_G5") (pintype "bidirectional"))
      (node (ref "IC1") (pin "G6") (pinfunction "VA19_4_G6") (pintype "bidirectional"))
      (node (ref "IC1") (pin "H3") (pinfunction "VA19_5_H3") (pintype "bidirectional"))
      (node (ref "IC1") (pin "H4") (pinfunction "VA19_6_H4") (pintype "bidirectional"))
      (node (ref "IC1") (pin "H5") (pinfunction "VA19_7_H5") (pintype "bidirectional"))
      (node (ref "IC1") (pin "H6") (pinfunction "VA19_8_H6") (pintype "bidirectional"))
      (node (ref "IC1") (pin "J3") (pinfunction "VA19_9_J3") (pintype "bidirectional"))
      (node (ref "IC1") (pin "J4") (pinfunction "VA19_10_J4") (pintype "bidirectional"))
      (node (ref "IC1") (pin "J5") (pinfunction "VA19_11_J5") (pintype "bidirectional"))
      (node (ref "IC1") (pin "J6") (pinfunction "VA19_12_J6") (pintype "bidirectional"))
      (node (ref "IC1") (pin "K3") (pinfunction "VA19_13_K3") (pintype "bidirectional"))
      (node (ref "IC1") (pin "K4") (pinfunction "VA19_14_K4") (pintype "bidirectional"))
      (node (ref "IC1") (pin "K5") (pinfunction "VA19_15_K5") (pintype "bidirectional"))
      (node (ref "IC1") (pin "K6") (pinfunction "VA19_16_K6") (pintype "bidirectional"))
      (node (ref "J1") (pin "5") (pinfunction "5_5") (pintype "passive"))
      (node (ref "J1") (pin "6") (pinfunction "6_6") (pintype "passive"))
      (node (ref "J1") (pin "7") (pinfunction "7_7") (pintype "passive"))
      (node (ref "J1") (pin "8") (pinfunction "8_8") (pintype "passive"))
      (node (ref "J12") (pin "4") (pinfunction "4_4") (pintype "passive"))
      (node (ref "R42") (pin "P$1") (pinfunction "P$1_P$1") (pintype "bidirectional"))
    )
    (net (code "246") (name "VD11") (class "Default")
      (node (ref "C24") (pin "2") (pinfunction "2_2") (pintype "passive"))
      (node (ref "C30") (pin "2") (pinfunction "2_2") (pintype "passive"))
      (node (ref "C31") (pin "2") (pinfunction "2_2") (pintype "passive"))
      (node (ref "C45") (pin "3") (pinfunction "OUT_3") (pintype "bidirectional"))
      (node (ref "C48") (pin "2") (pinfunction "2_2") (pintype "passive"))
      (node (ref "C49") (pin "2") (pinfunction "2_2") (pintype "passive"))
      (node (ref "IC1") (pin "E8") (pinfunction "VD11_1_E8") (pintype "bidirectional"))
      (node (ref "IC1") (pin "F8") (pinfunction "VD11_2_F8") (pintype "bidirectional"))
      (node (ref "IC1") (pin "G8") (pinfunction "VD11_3_G8") (pintype "bidirectional"))
      (node (ref "IC1") (pin "K8") (pinfunction "VD11_4_K8") (pintype "bidirectional"))
      (node (ref "IC1") (pin "L8") (pinfunction "VD11_5_L8") (pintype "bidirectional"))
      (node (ref "IC1") (pin "M8") (pinfunction "VD11_6_M8") (pintype "bidirectional"))
      (node (ref "J3") (pin "5") (pinfunction "5_5") (pintype "passive"))
      (node (ref "J3") (pin "6") (pinfunction "6_6") (pintype "passive"))
      (node (ref "J3") (pin "7") (pinfunction "7_7") (pintype "passive"))
      (node (ref "J3") (pin "8") (pinfunction "8_8") (pintype "passive"))
    )
    (net (code "247") (name "VDDD33") (class "Default")
      (node (ref "C3") (pin "2") (pinfunction "2_2") (pintype "passive"))
      (node (ref "IC2") (pin "1") (pinfunction "DIR1_1") (pintype "bidirectional"))
      (node (ref "IC2") (pin "16") (pinfunction "VCCA_16") (pintype "bidirectional"))
      (node (ref "IC2") (pin "2") (pinfunction "DIR2_2") (pintype "bidirectional"))
      (node (ref "IC2") (pin "7") (pinfunction "DIR3_7") (pintype "bidirectional"))
      (node (ref "J12") (pin "2") (pinfunction "2_2") (pintype "passive"))
      (node (ref "J2") (pin "3") (pinfunction "3_3") (pintype "passive"))
      (node (ref "J2") (pin "4") (pinfunction "4_4") (pintype "passive"))
      (node (ref "J4") (pin "1") (pinfunction "1_1") (pintype "passive"))
      (node (ref "J4") (pin "7") (pinfunction "7_7") (pintype "passive"))
      (node (ref "R44") (pin "P$1") (pinfunction "P$1_P$1") (pintype "bidirectional"))
    )
    (net (code "248") (name "VDDL19") (class "Default")
      (node (ref "C15") (pin "3") (pinfunction "OUT_3") (pintype "bidirectional"))
      (node (ref "C18") (pin "2") (pinfunction "2_2") (pintype "passive"))
      (node (ref "C19") (pin "2") (pinfunction "2_2") (pintype "passive"))
      (node (ref "C4") (pin "2") (pinfunction "2_2") (pintype "passive"))
      (node (ref "IC2") (pin "15") (pinfunction "VCCB_15") (pintype "bidirectional"))
      (node (ref "J12") (pin "3") (pinfunction "3_3") (pintype "passive"))
      (node (ref "J2") (pin "1") (pinfunction "1_1") (pintype "passive"))
      (node (ref "J2") (pin "2") (pinfunction "2_2") (pintype "passive"))
      (node (ref "R43") (pin "P$1") (pinfunction "P$1_P$1") (pintype "bidirectional"))
      (node (ref "R5") (pin "P$1") (pinfunction "P$1_P$1") (pintype "bidirectional"))
    )
    (net (code "249") (name "VLVDS") (class "Default")
      (node (ref "C10") (pin "2") (pinfunction "2_2") (pintype "passive"))
      (node (ref "C11") (pin "2") (pinfunction "2_2") (pintype "passive"))
      (node (ref "C12") (pin "2") (pinfunction "2_2") (pintype "passive"))
      (node (ref "C5") (pin "3") (pinfunction "OUT_3") (pintype "bidirectional"))
      (node (ref "C8") (pin "2") (pinfunction "2_2") (pintype "passive"))
      (node (ref "C9") (pin "2") (pinfunction "2_2") (pintype "passive"))
      (node (ref "IC1") (pin "G11") (pinfunction "VLVDS_1_G11") (pintype "bidirectional"))
      (node (ref "IC1") (pin "G12") (pinfunction "VLVDS_2_G12") (pintype "bidirectional"))
      (node (ref "IC1") (pin "H11") (pinfunction "VLVDS_3_H11") (pintype "bidirectional"))
      (node (ref "IC1") (pin "H12") (pinfunction "VLVDS_4_H12") (pintype "bidirectional"))
      (node (ref "IC1") (pin "H13") (pinfunction "VLVDS_5_H13") (pintype "bidirectional"))
      (node (ref "IC1") (pin "J11") (pinfunction "VLVDS_6_J11") (pintype "bidirectional"))
      (node (ref "IC1") (pin "J12") (pinfunction "VLVDS_7_J12") (pintype "bidirectional"))
      (node (ref "IC1") (pin "J13") (pinfunction "VLVDS_8_J13") (pintype "bidirectional"))
      (node (ref "IC1") (pin "K11") (pinfunction "VLVDS_9_K11") (pintype "bidirectional"))
      (node (ref "IC1") (pin "K12") (pinfunction "VLVDS_10_K12") (pintype "bidirectional"))
      (node (ref "J1") (pin "1") (pinfunction "1_1") (pintype "passive"))
      (node (ref "J1") (pin "2") (pinfunction "2_2") (pintype "passive"))
      (node (ref "J1") (pin "3") (pinfunction "3_3") (pintype "passive"))
      (node (ref "J1") (pin "4") (pinfunction "4_4") (pintype "passive"))
    )
    (net (code "250") (name "VLVDS_IN") (class "Default")
      (node (ref "C5") (pin "1") (pinfunction "IN_1") (pintype "bidirectional"))
      (node (ref "C6") (pin "2") (pinfunction "2_2") (pintype "passive"))
      (node (ref "C7") (pin "2") (pinfunction "2_2") (pintype "passive"))
      (node (ref "J5") (pin "2") (pinfunction "2_2") (pintype "passive"))
    )
    (net (code "251") (name "unconnected-(X14T-S-Pad27)") (class "Default")
      (node (ref "X14") (pin "27") (pinfunction "S_27") (pintype "passive"))
    )
    (net (code "252") (name "unconnected-(X14U-S-Pad28)") (class "Default")
      (node (ref "X14") (pin "28") (pinfunction "S_28") (pintype "passive"))
    )
    (net (code "253") (name "unconnected-(X17T-S-Pad27)") (class "Default")
      (node (ref "X17") (pin "27") (pinfunction "S_27") (pintype "passive"))
    )
    (net (code "254") (name "unconnected-(X17U-S-Pad28)") (class "Default")
      (node (ref "X17") (pin "28") (pinfunction "S_28") (pintype "passive"))
    )
  )
)
